# amp_diagram.net
KiCad netlist of a schematic drawn in EAGLE
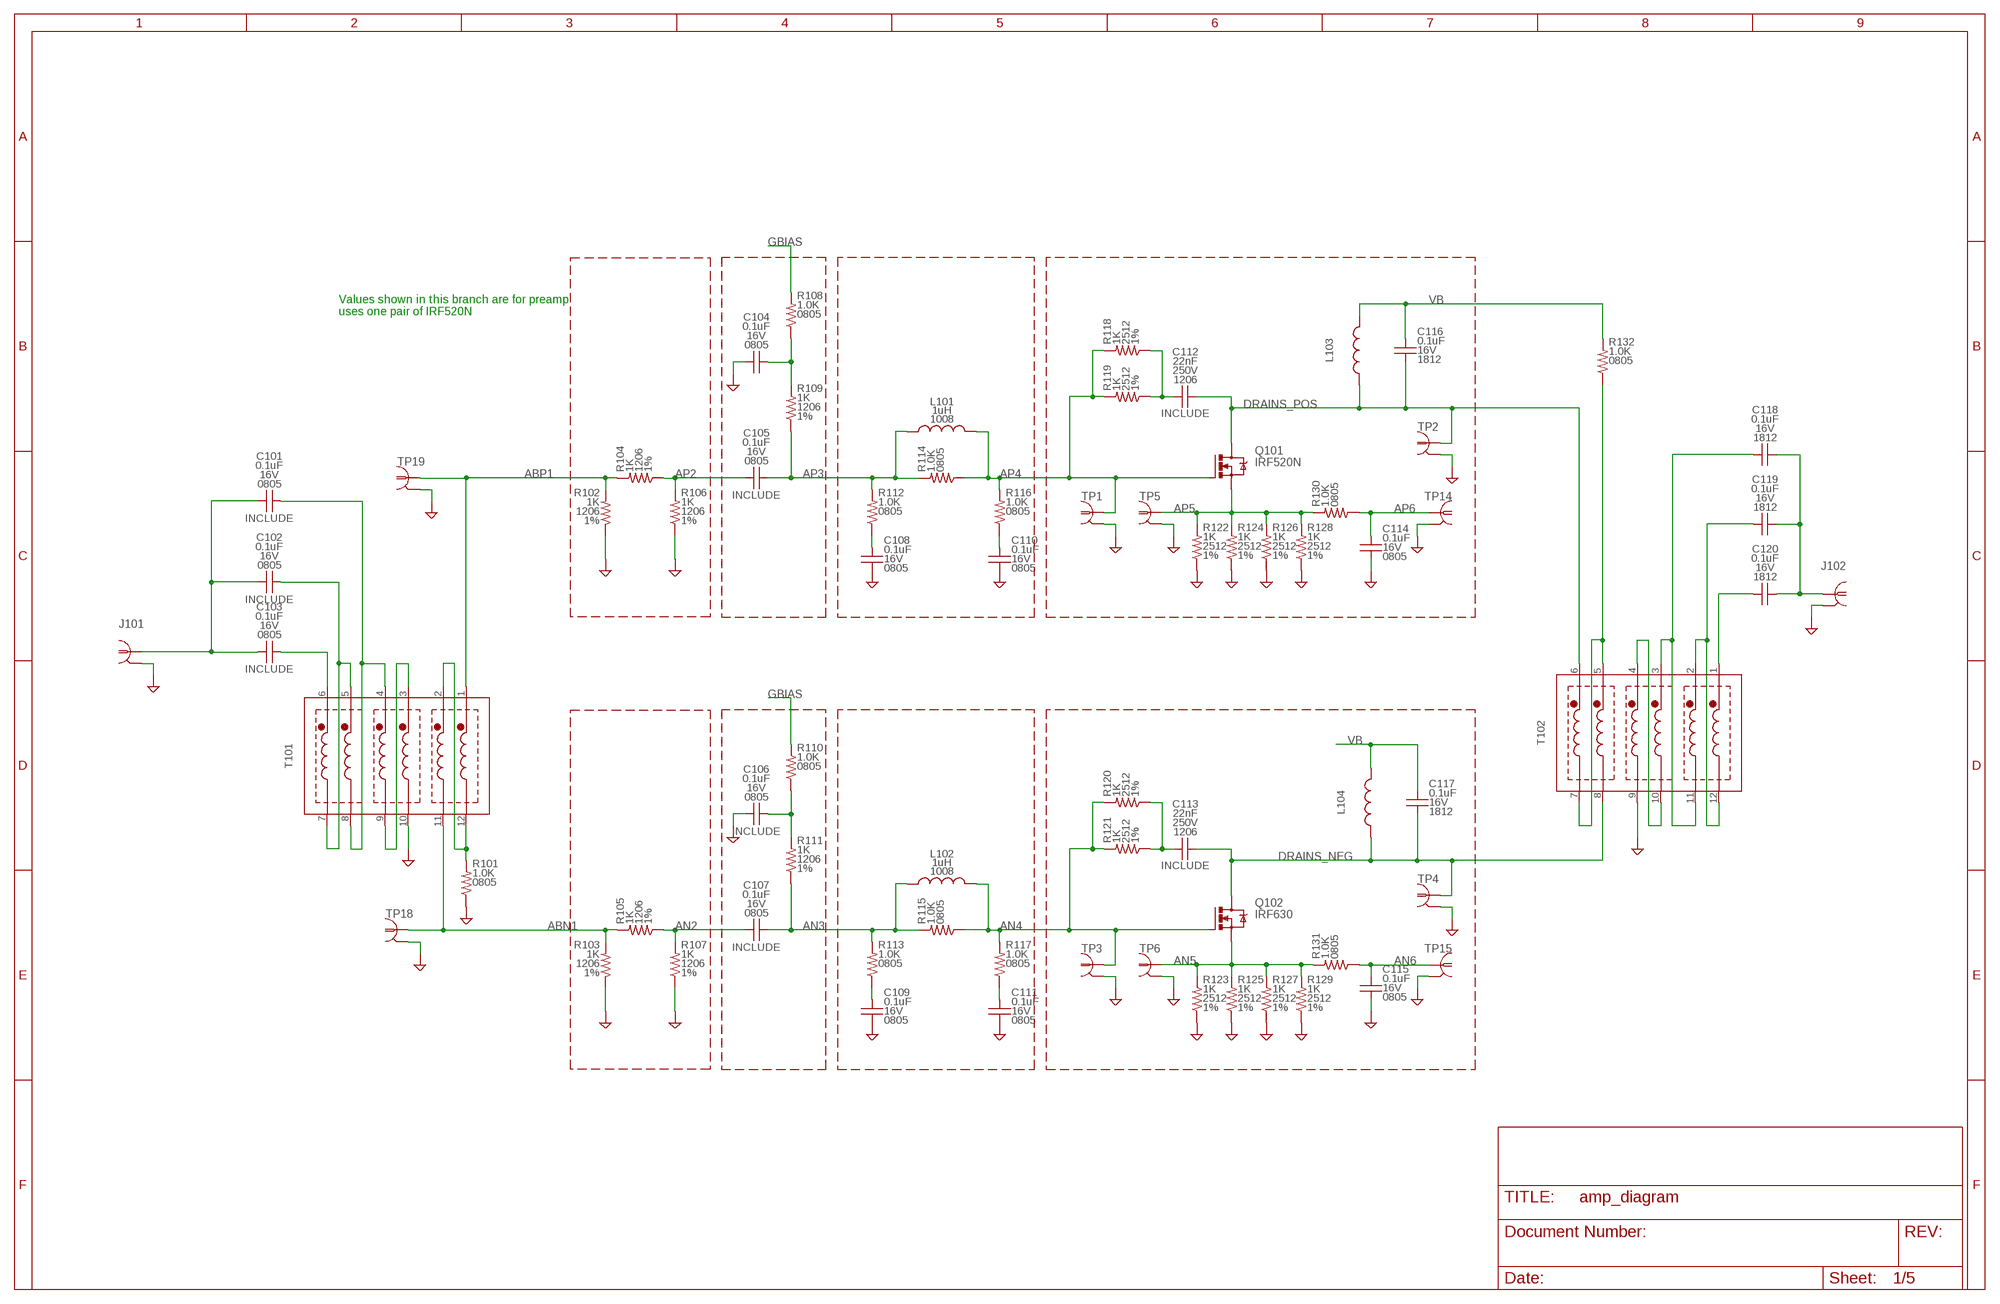
[diagram p0: schematic, sheet 1, part 1 of 2]
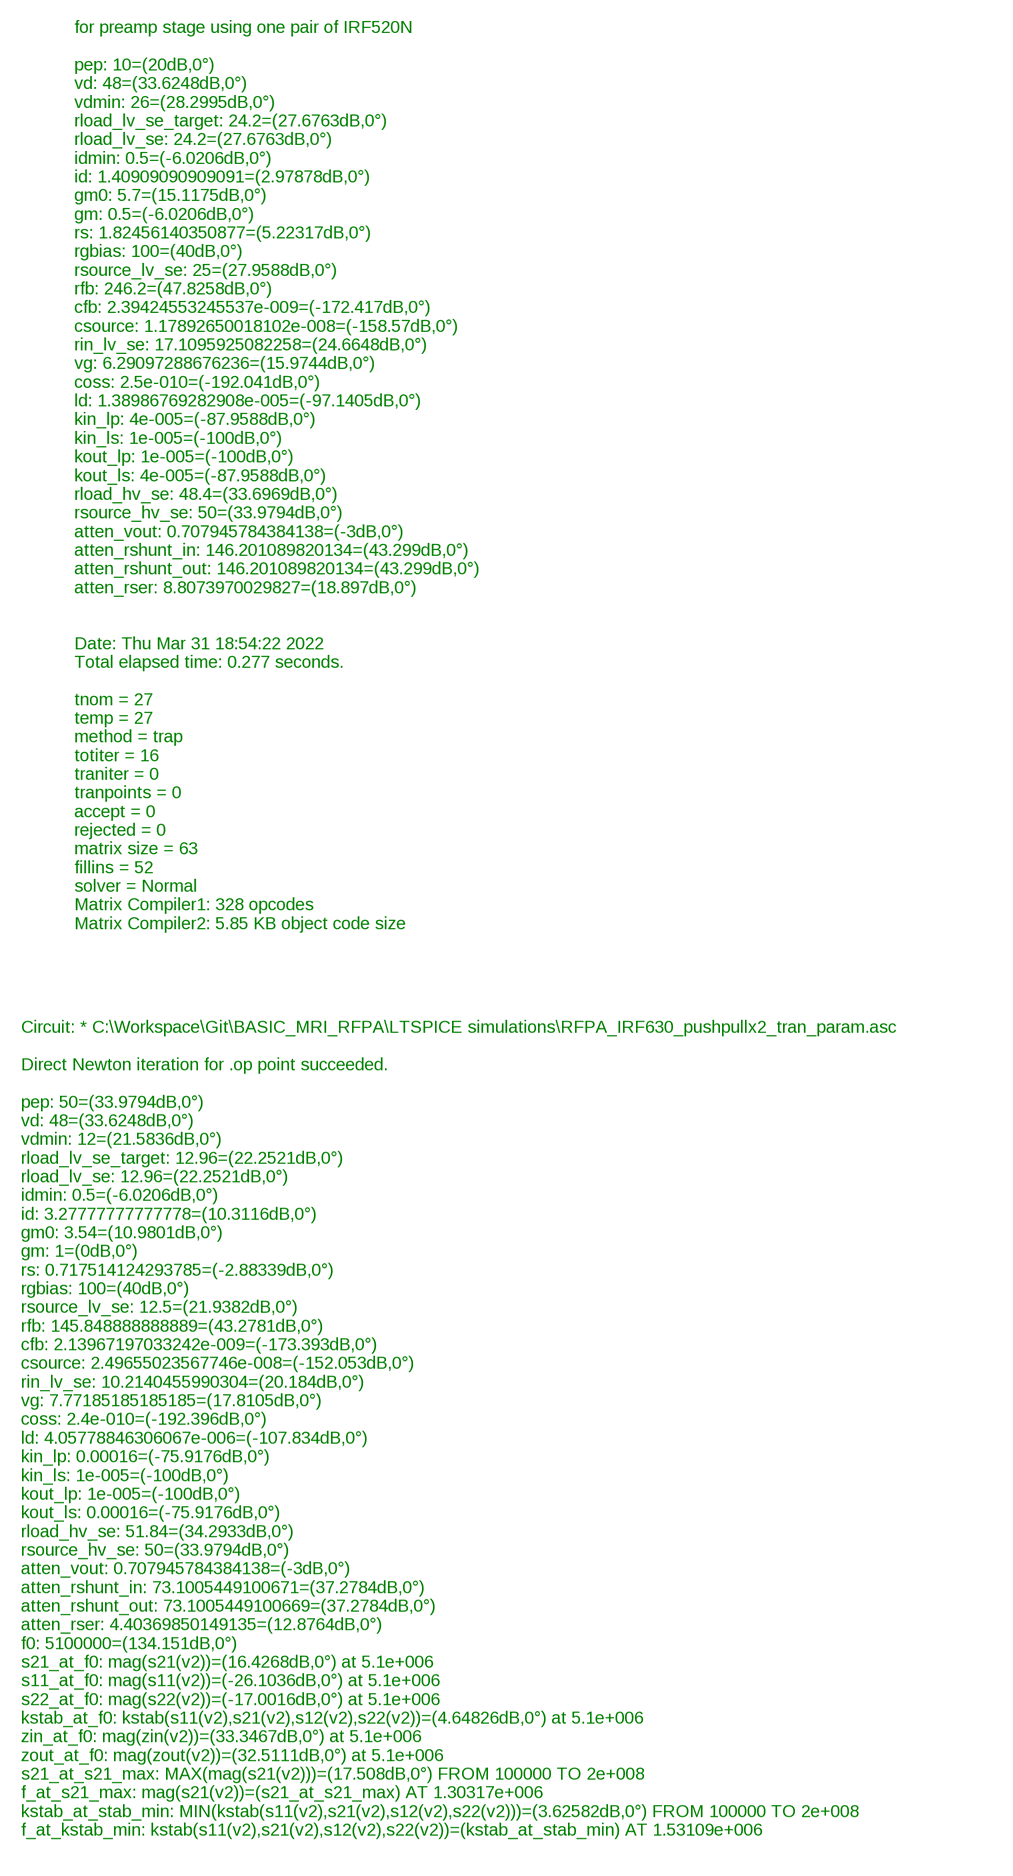
[diagram p1: schematic, sheet 1, part 2 of 2]
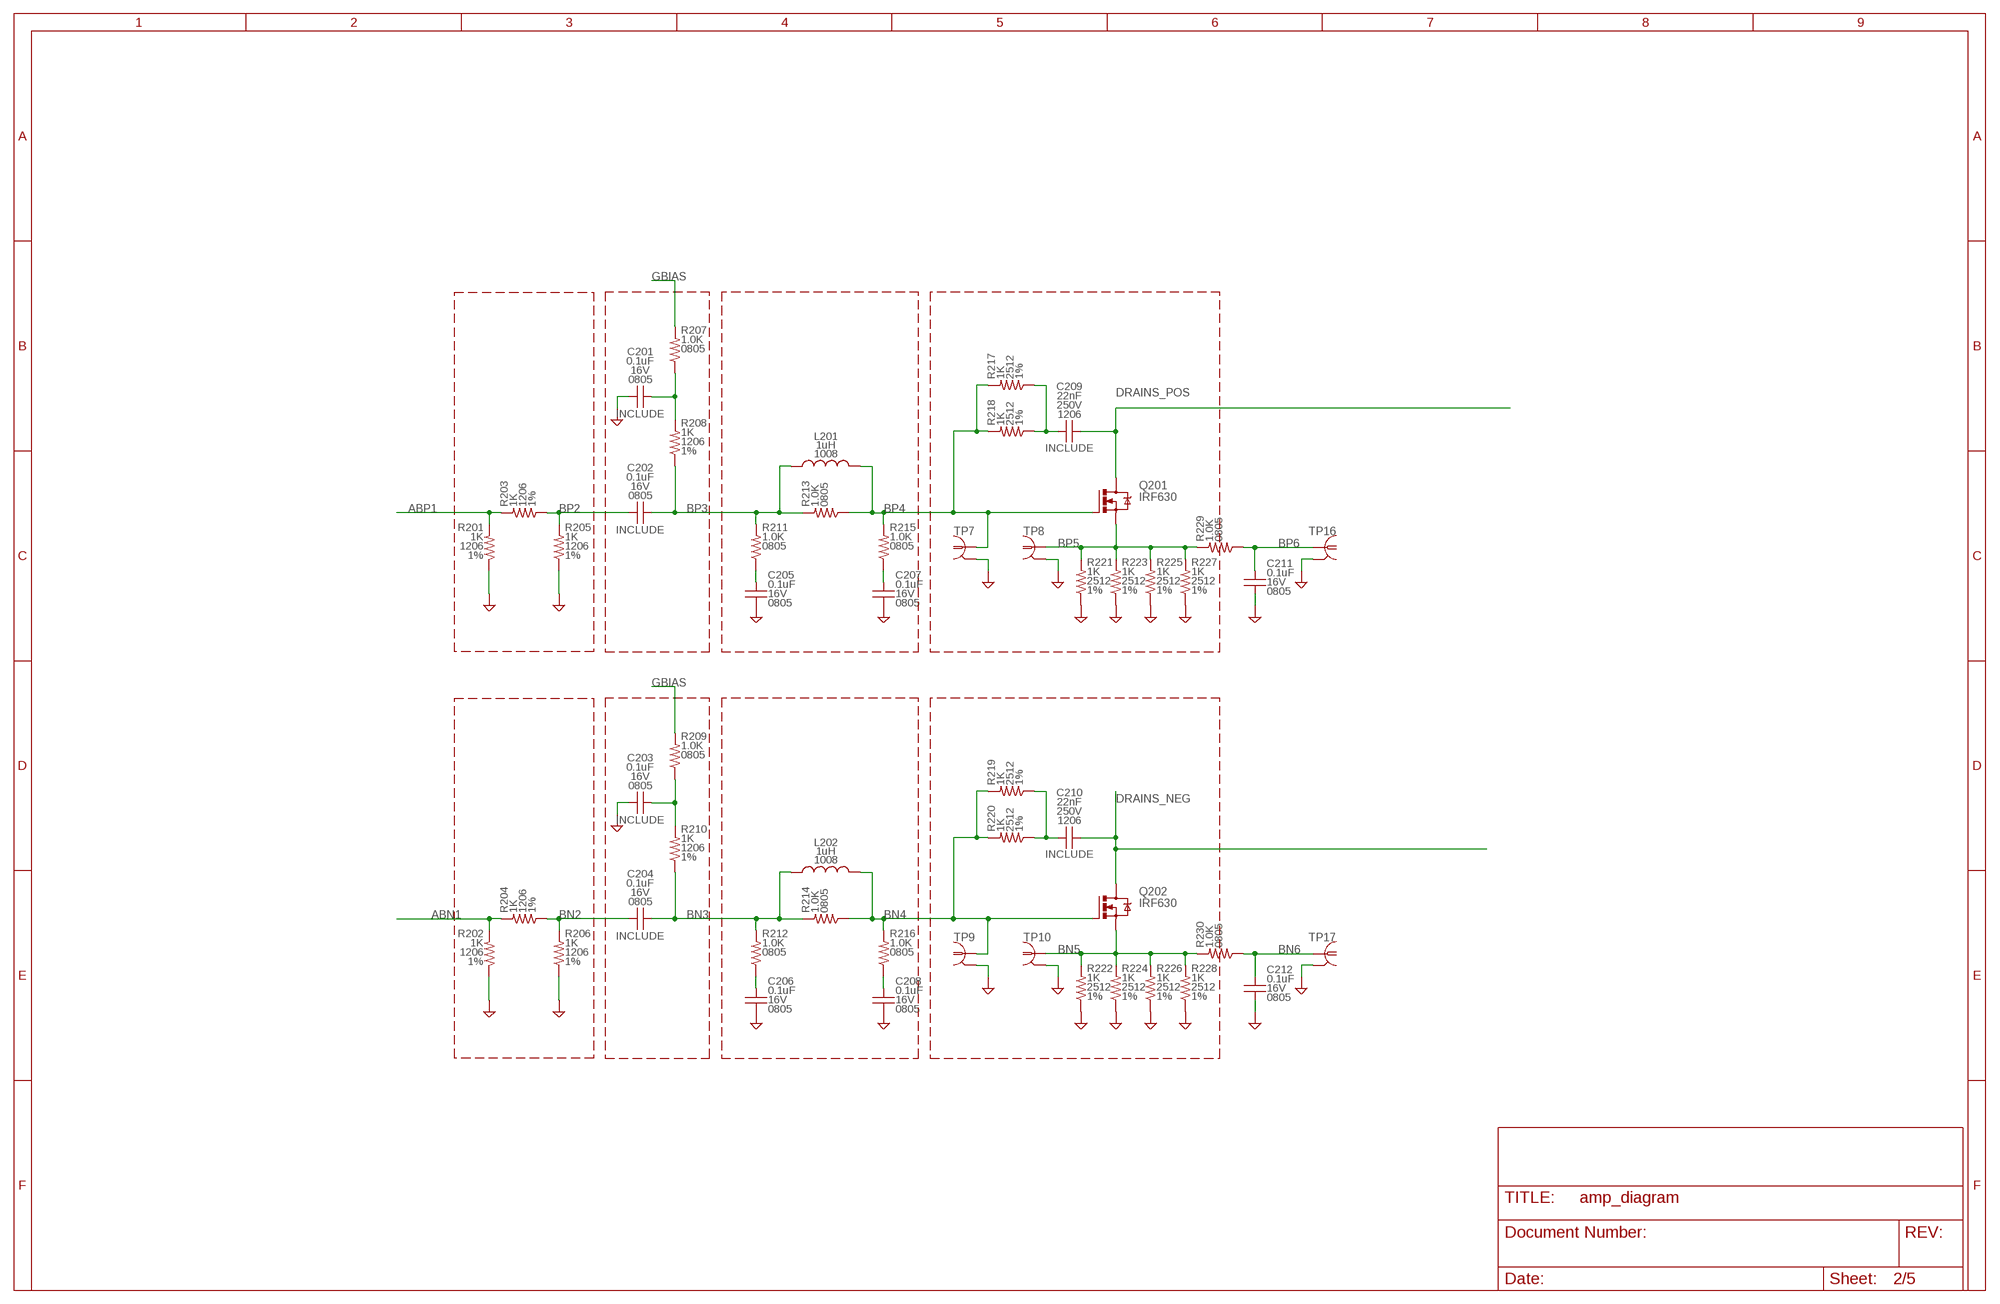
[diagram p2: schematic, sheet 2]
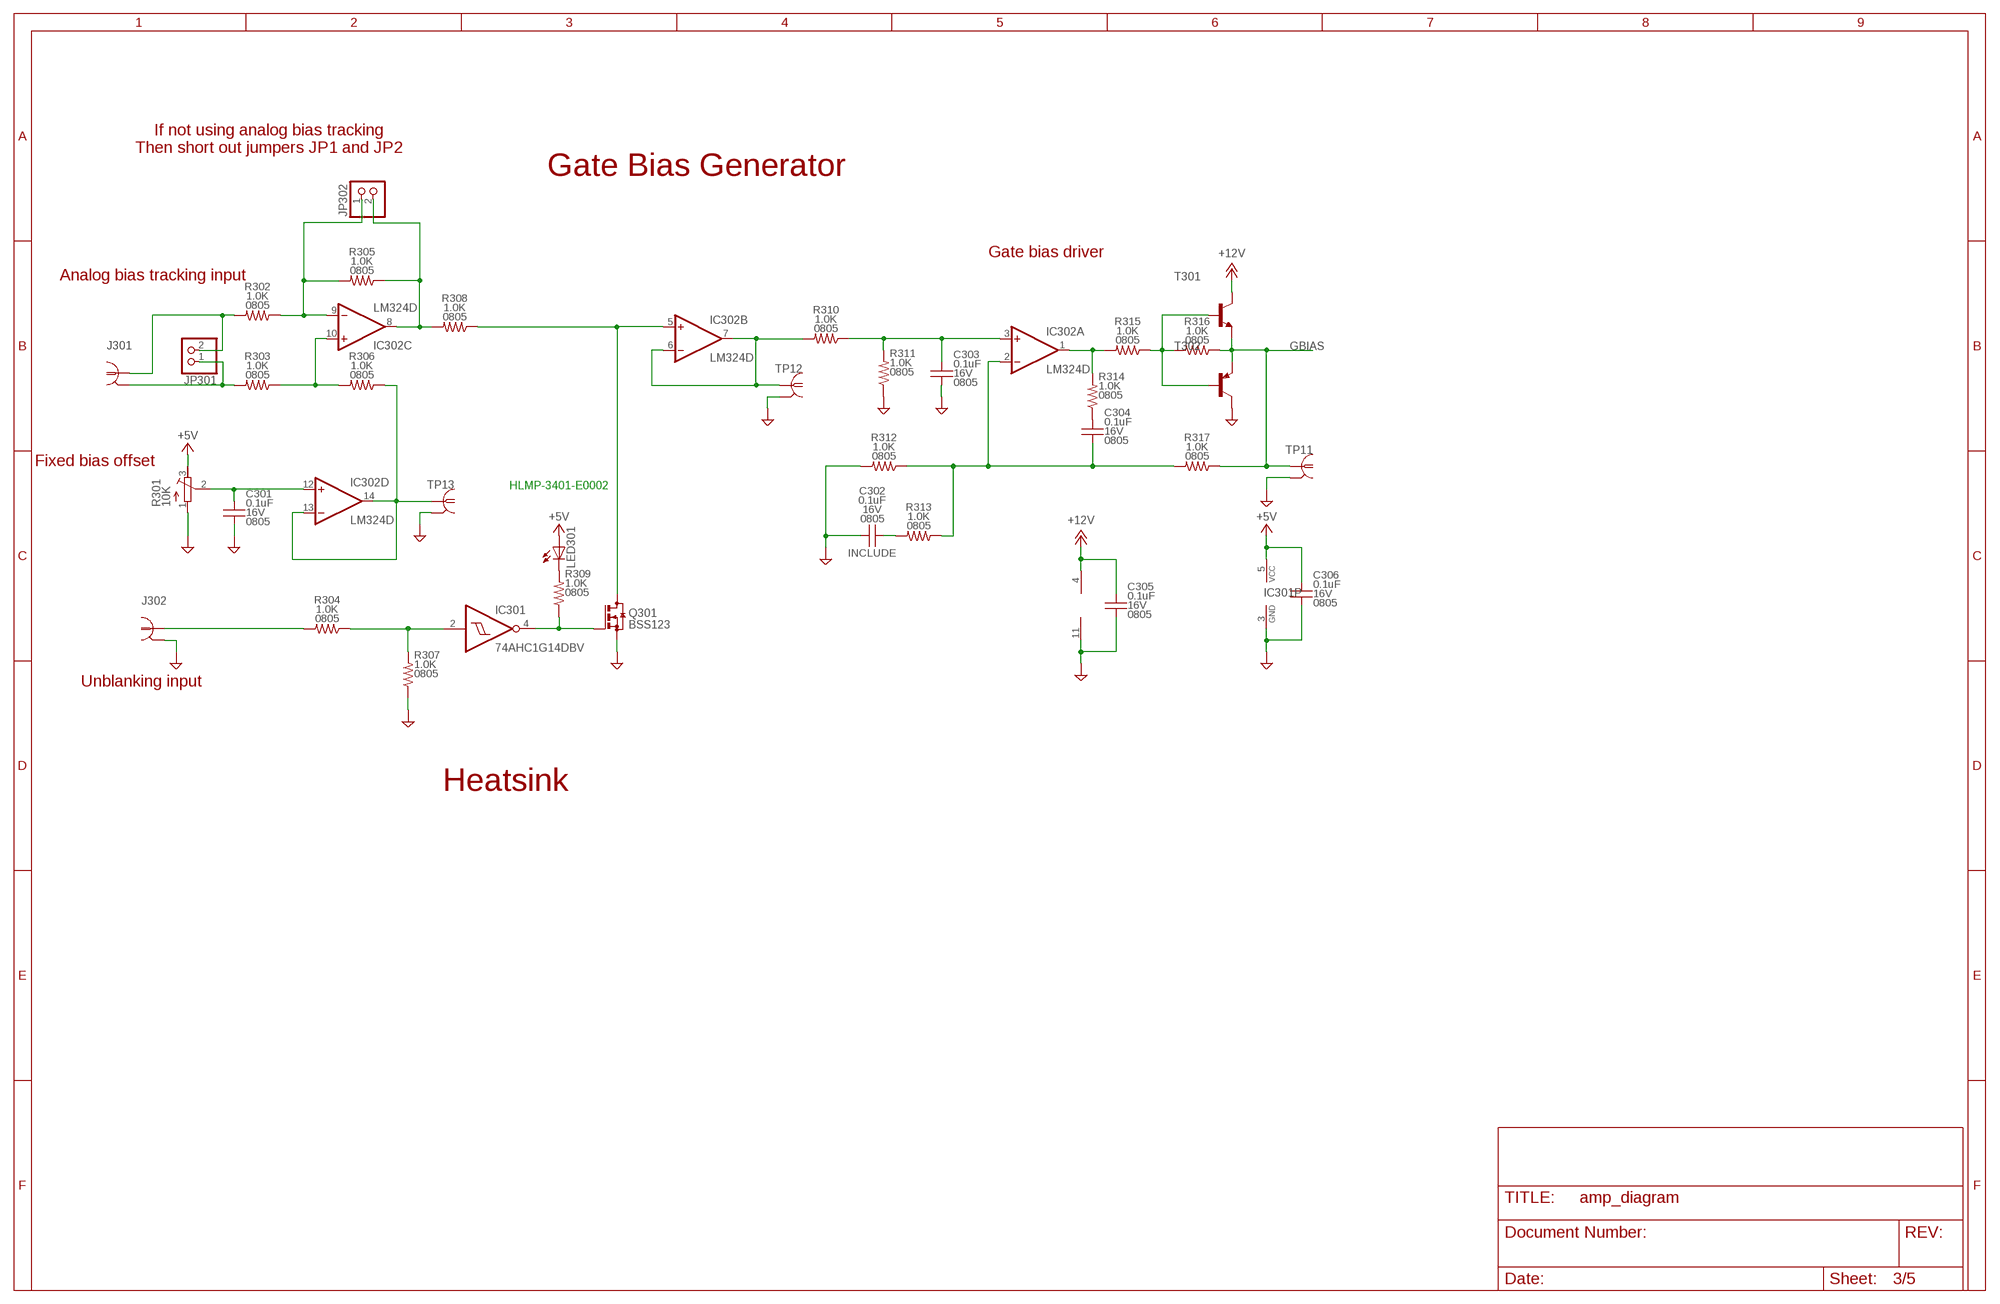
[diagram p3: schematic, sheet 3]
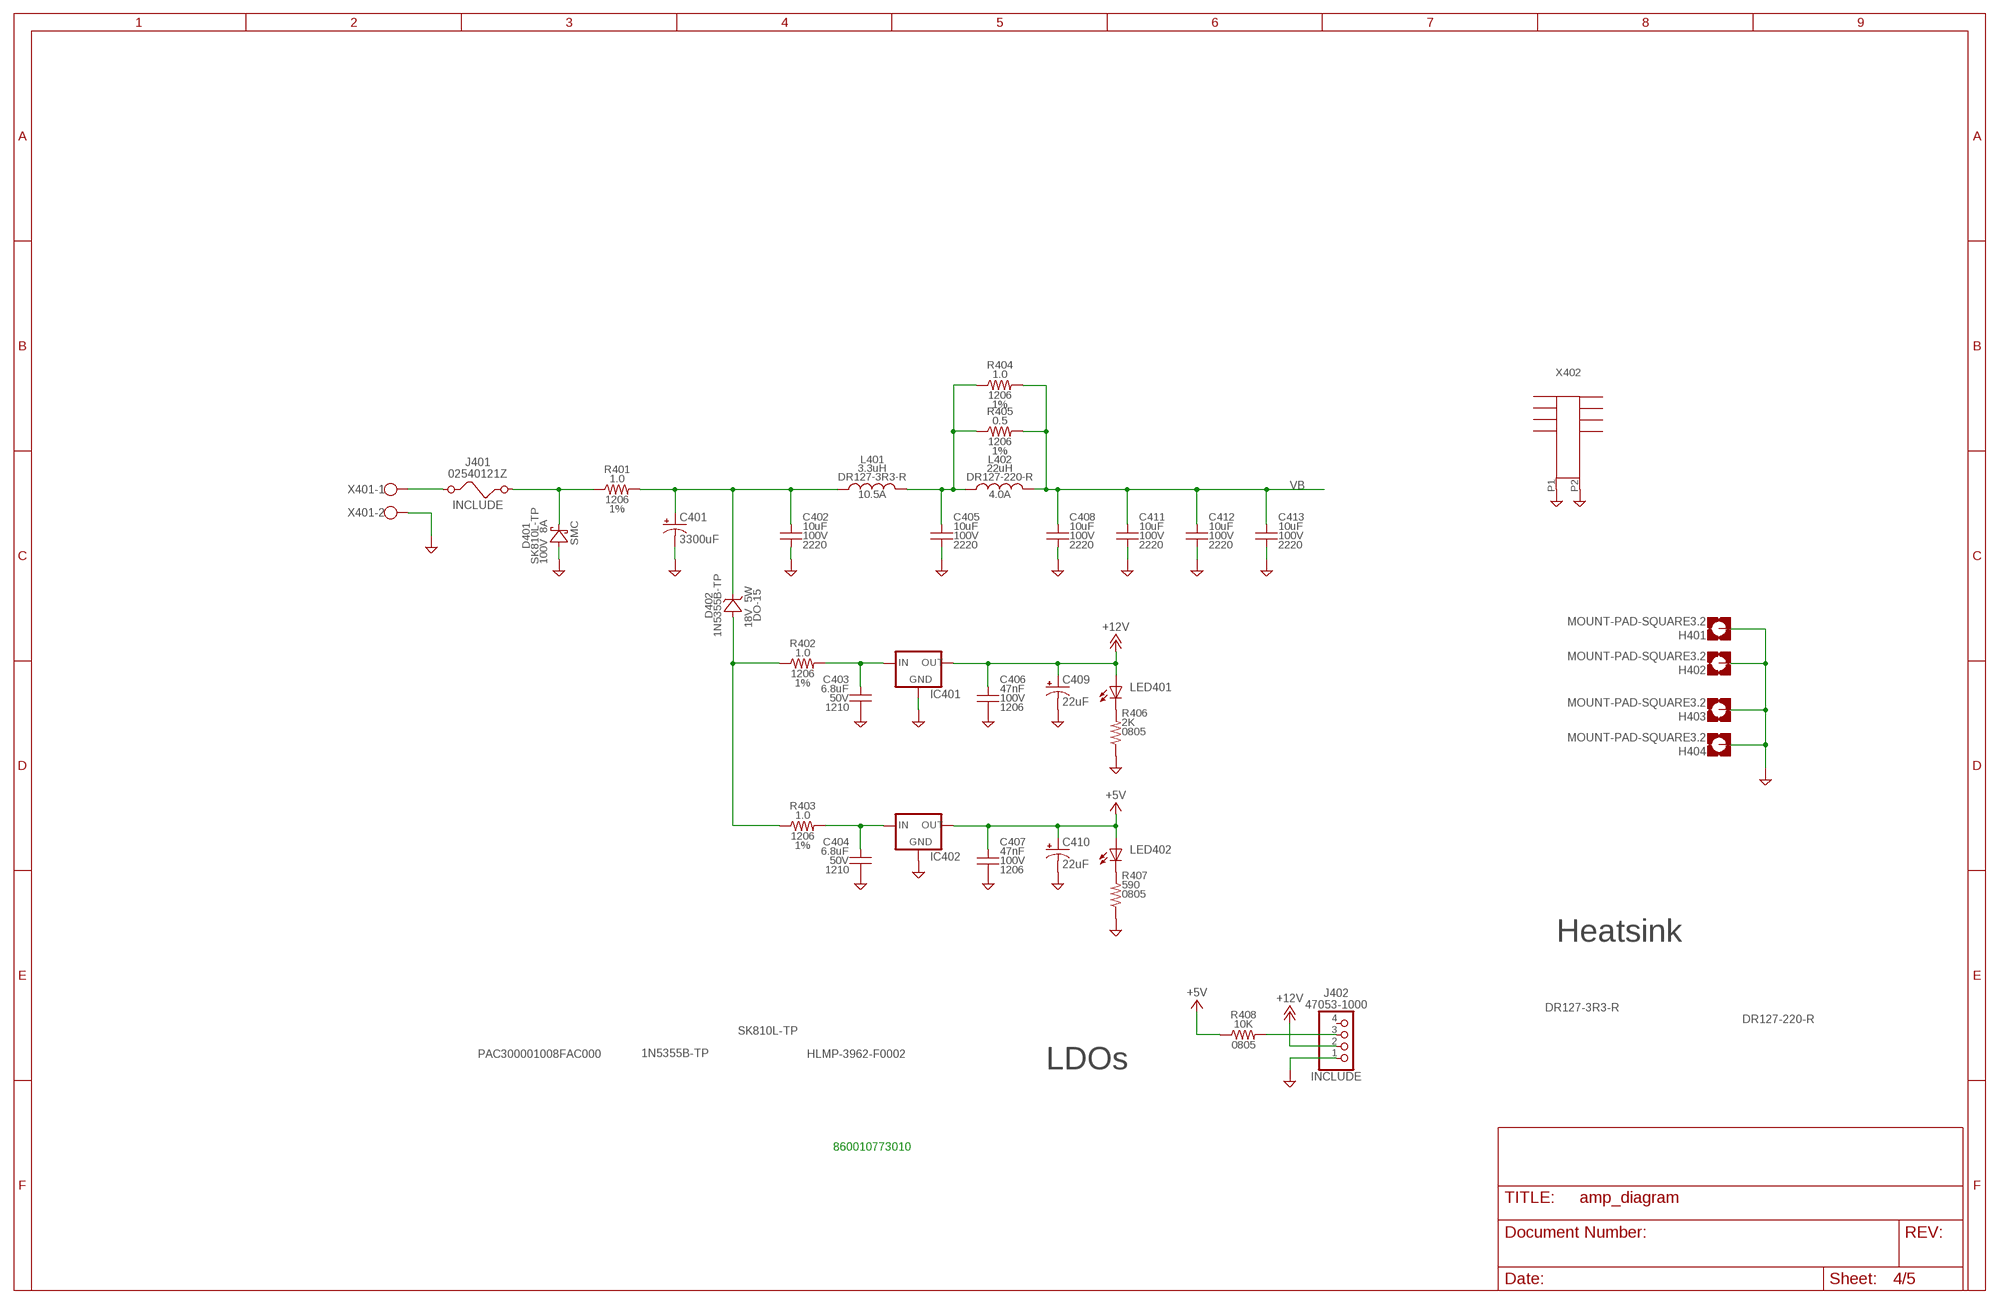
[diagram p4: schematic, sheet 4]
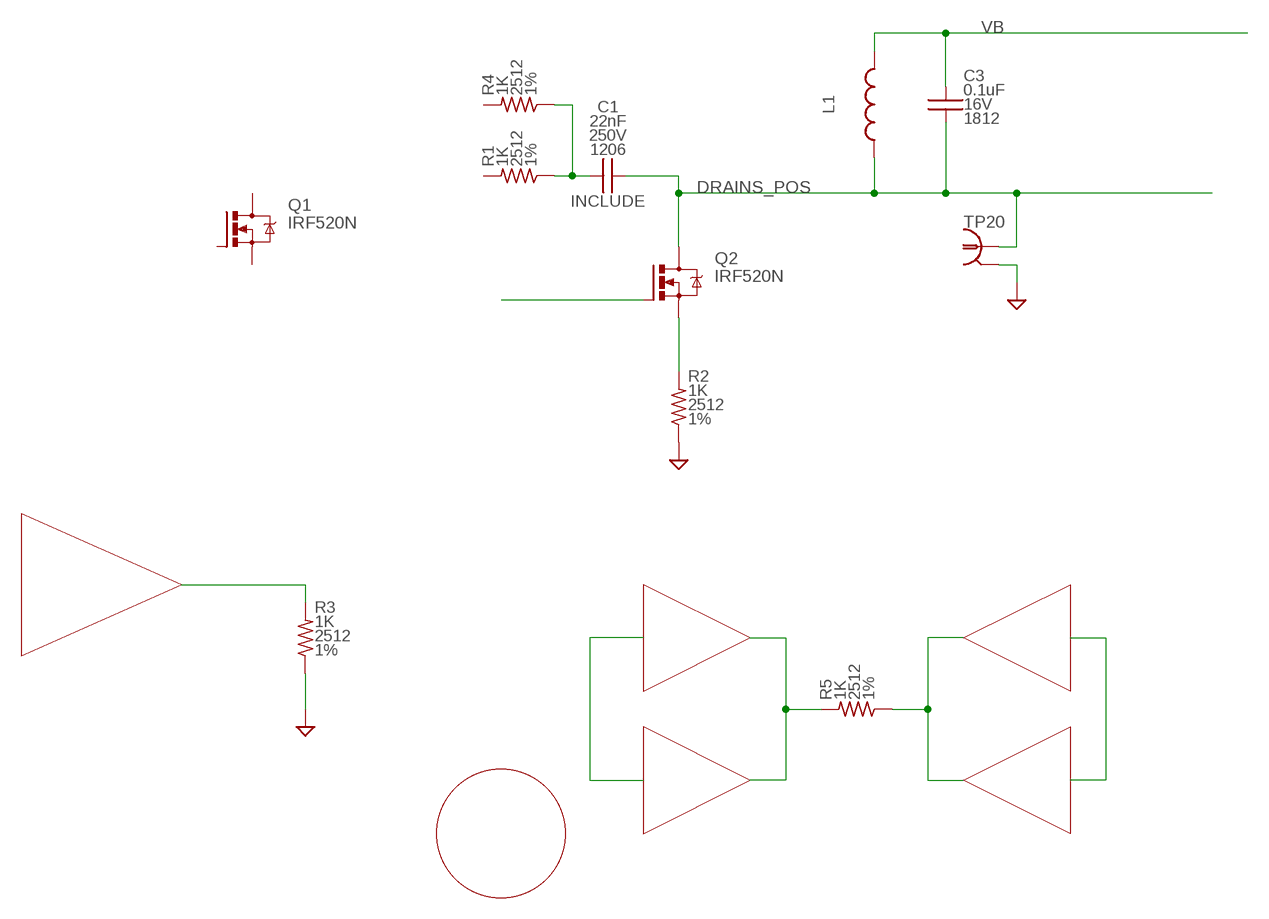
[diagram p5: schematic, sheet 5]

(export (version "E")
  (design (tool "Eeschema 10.0.6"))
  (components
    (comp (ref "C1")
      (value "22nF")
      (footprint "eagle-import:C1206")
      (fields
        (field (name "BOM") "INCLUDE")
        (field (name "PACKAGE") "1206")
        (field (name "PARTNO") "C3216NP02E223J160AA")
        (field (name "VOLTAGE") "250V")
      )
      (libsource (lib "eagle-import") (part "CC1206C-22N-250V-5%-1206-NP0"))
    )
    (comp (ref "C3")
      (value "0.1uF")
      (footprint "eagle-import:C1812")
      (fields (field (name "VOLTAGE") "16V"))
      (libsource (lib "eagle-import") (part "CC1812"))
    )
    (comp (ref "L1") (value "L") (footprint "eagle-import:DR127") (libsource (lib "eagle-import") (part "L")))
    (comp (ref "Q1")
      (value "IRF520N")
      (footprint "eagle-import:TO220BV")
      (libsource (lib "eagle-import") (part "IRF540"))
    )
    (comp (ref "Q2")
      (value "IRF520N")
      (footprint "eagle-import:TO220BV")
      (libsource (lib "eagle-import") (part "IRF540"))
    )
    (comp (ref "R1")
      (value "1K")
      (footprint "eagle-import:R2512")
      (fields (field (name "POWER") "1"))
      (libsource (lib "eagle-import") (part "RR2512R-1K-1%-2512-1W"))
    )
    (comp (ref "R2")
      (value "1K")
      (footprint "eagle-import:R2512")
      (fields (field (name "POWER") "1"))
      (libsource (lib "eagle-import") (part "RR2512R-1K-1%-2512-1W"))
    )
    (comp (ref "R3")
      (value "1K")
      (footprint "eagle-import:R2512")
      (fields (field (name "POWER") "1"))
      (libsource (lib "eagle-import") (part "RR2512R-1K-1%-2512-1W"))
    )
    (comp (ref "R4")
      (value "1K")
      (footprint "eagle-import:R2512")
      (fields (field (name "POWER") "1"))
      (libsource (lib "eagle-import") (part "RR2512R-1K-1%-2512-1W"))
    )
    (comp (ref "R5")
      (value "1K")
      (footprint "eagle-import:R2512")
      (fields (field (name "POWER") "1"))
      (libsource (lib "eagle-import") (part "RR2512R-1K-1%-2512-1W"))
    )
    (comp (ref "TP20")
      (value "PROBE_TPTP_7P5MM")
      (footprint "eagle-import:PROBE_TP_7P5MM")
      (libsource (lib "eagle-import") (part "PROBE_TPTP_7P5MM"))
    )
    (comp (ref "C301")
      (value "0.1uF")
      (footprint "eagle-import:0805_IPC-7351B")
      (fields (field (name "VOLTAGE") "16V"))
      (libsource (lib "eagle-import") (part "C0805_IPCC-0.1U-16V-0805-X7R"))
    )
    (comp (ref "C302")
      (value "0.1uF")
      (footprint "eagle-import:0805_IPC-7351B")
      (fields (field (name "PACKAGE") "0805") (field (name "VOLTAGE") "16V") (field (name "BOM") "INCLUDE"))
      (libsource (lib "eagle-import") (part "C0805_IPCC-0.1U-16V-0805-X7R"))
    )
    (comp (ref "C303")
      (value "0.1uF")
      (footprint "eagle-import:0805_IPC-7351B")
      (fields (field (name "VOLTAGE") "16V"))
      (libsource (lib "eagle-import") (part "C0805_IPCC-0.1U-16V-0805-X7R"))
    )
    (comp (ref "C304")
      (value "0.1uF")
      (footprint "eagle-import:0805_IPC-7351B")
      (fields (field (name "VOLTAGE") "16V"))
      (libsource (lib "eagle-import") (part "C0805_IPCC-0.1U-16V-0805-X7R"))
    )
    (comp (ref "C305")
      (value "0.1uF")
      (footprint "eagle-import:0805_IPC-7351B")
      (fields (field (name "VOLTAGE") "16V"))
      (libsource (lib "eagle-import") (part "C0805_IPCC-0.1U-16V-0805-X7R"))
    )
    (comp (ref "C306")
      (value "0.1uF")
      (footprint "eagle-import:0805_IPC-7351B")
      (fields (field (name "VOLTAGE") "16V"))
      (libsource (lib "eagle-import") (part "C0805_IPCC-0.1U-16V-0805-X7R"))
    )
    (comp (ref "IC301")
      (value "74AHC1G14DBV")
      (footprint "eagle-import:SOT23-5")
      (libsource (lib "eagle-import") (part "741G14DBVAHC"))
    )
    (comp (ref "IC302")
      (value "LM324D")
      (footprint "eagle-import:SO14")
      (libsource (lib "eagle-import") (part "LM324D"))
    )
    (comp (ref "J301")
      (value "COAXBNC_EDGE")
      (footprint "eagle-import:BNC_EDGE")
      (libsource (lib "eagle-import") (part "COAXBNC_EDGE"))
    )
    (comp (ref "J302")
      (value "COAXBNC_EDGE")
      (footprint "eagle-import:BNC_EDGE")
      (libsource (lib "eagle-import") (part "COAXBNC_EDGE"))
    )
    (comp (ref "JP301")
      (value "PINHD-1X2")
      (footprint "eagle-import:1X02")
      (libsource (lib "eagle-import") (part "PINHD-1X2"))
    )
    (comp (ref "JP302")
      (value "PINHD-1X2")
      (footprint "eagle-import:1X02")
      (libsource (lib "eagle-import") (part "PINHD-1X2"))
    )
    (comp (ref "LED301")
      (value "LED5MM")
      (footprint "eagle-import:LED5MM")
      (libsource (lib "eagle-import") (part "LED5MM"))
    )
    (comp (ref "Q301")
      (value "BSS123")
      (footprint "eagle-import:SOT23")
      (libsource (lib "eagle-import") (part "BSS123"))
    )
    (comp (ref "R301")
      (value "10K")
      (footprint "eagle-import:RTRIM3299W")
      (libsource (lib "eagle-import") (part "R-TRIMM3299W"))
    )
    (comp (ref "R302")
      (value "1.0K")
      (footprint "eagle-import:0805_IPC-7351B")
      (fields (field (name "PACKAGE") "0805"))
      (libsource (lib "eagle-import") (part "R0805_IPCR-1.0K-0.1%-0805-0.1W"))
    )
    (comp (ref "R303")
      (value "1.0K")
      (footprint "eagle-import:0805_IPC-7351B")
      (fields (field (name "PACKAGE") "0805"))
      (libsource (lib "eagle-import") (part "R0805_IPCR-1.0K-0.1%-0805-0.1W"))
    )
    (comp (ref "R304")
      (value "1.0K")
      (footprint "eagle-import:0805_IPC-7351B")
      (fields (field (name "PACKAGE") "0805"))
      (libsource (lib "eagle-import") (part "R0805_IPCR-1.0K-0.1%-0805-0.1W"))
    )
    (comp (ref "R305")
      (value "1.0K")
      (footprint "eagle-import:0805_IPC-7351B")
      (fields (field (name "PACKAGE") "0805"))
      (libsource (lib "eagle-import") (part "R0805_IPCR-1.0K-0.1%-0805-0.1W"))
    )
    (comp (ref "R306")
      (value "1.0K")
      (footprint "eagle-import:0805_IPC-7351B")
      (fields (field (name "PACKAGE") "0805"))
      (libsource (lib "eagle-import") (part "R0805_IPCR-1.0K-0.1%-0805-0.1W"))
    )
    (comp (ref "R307")
      (value "1.0K")
      (footprint "eagle-import:0805_IPC-7351B")
      (libsource (lib "eagle-import") (part "R0805_IPCR-1.0K-0.1%-0805-0.1W"))
    )
    (comp (ref "R308")
      (value "1.0K")
      (footprint "eagle-import:0805_IPC-7351B")
      (fields (field (name "PACKAGE") "0805"))
      (libsource (lib "eagle-import") (part "R0805_IPCR-1.0K-0.1%-0805-0.1W"))
    )
    (comp (ref "R309")
      (value "1.0K")
      (footprint "eagle-import:0805_IPC-7351B")
      (libsource (lib "eagle-import") (part "R0805_IPCR-1.0K-0.1%-0805-0.1W"))
    )
    (comp (ref "R310")
      (value "1.0K")
      (footprint "eagle-import:0805_IPC-7351B")
      (fields (field (name "PACKAGE") "0805"))
      (libsource (lib "eagle-import") (part "R0805_IPCR-1.0K-0.1%-0805-0.1W"))
    )
    (comp (ref "R311")
      (value "1.0K")
      (footprint "eagle-import:0805_IPC-7351B")
      (libsource (lib "eagle-import") (part "R0805_IPCR-1.0K-0.1%-0805-0.1W"))
    )
    (comp (ref "R312")
      (value "1.0K")
      (footprint "eagle-import:0805_IPC-7351B")
      (fields (field (name "PACKAGE") "0805"))
      (libsource (lib "eagle-import") (part "R0805_IPCR-1.0K-0.1%-0805-0.1W"))
    )
    (comp (ref "R313")
      (value "1.0K")
      (footprint "eagle-import:0805_IPC-7351B")
      (fields (field (name "PACKAGE") "0805"))
      (libsource (lib "eagle-import") (part "R0805_IPCR-1.0K-0.1%-0805-0.1W"))
    )
    (comp (ref "R314")
      (value "1.0K")
      (footprint "eagle-import:0805_IPC-7351B")
      (libsource (lib "eagle-import") (part "R0805_IPCR-1.0K-0.1%-0805-0.1W"))
    )
    (comp (ref "R315")
      (value "1.0K")
      (footprint "eagle-import:0805_IPC-7351B")
      (fields (field (name "PACKAGE") "0805"))
      (libsource (lib "eagle-import") (part "R0805_IPCR-1.0K-0.1%-0805-0.1W"))
    )
    (comp (ref "R316")
      (value "1.0K")
      (footprint "eagle-import:0805_IPC-7351B")
      (fields (field (name "PACKAGE") "0805"))
      (libsource (lib "eagle-import") (part "R0805_IPCR-1.0K-0.1%-0805-0.1W"))
    )
    (comp (ref "R317")
      (value "1.0K")
      (footprint "eagle-import:0805_IPC-7351B")
      (fields (field (name "PACKAGE") "0805"))
      (libsource (lib "eagle-import") (part "R0805_IPCR-1.0K-0.1%-0805-0.1W"))
    )
    (comp (ref "T301")
      (value "BC808-NPN-SOT23-BEC")
      (footprint "eagle-import:SOT23-BEC")
      (libsource (lib "eagle-import") (part "-NPN-SOT23-BECBC808"))
    )
    (comp (ref "T302")
      (value "BC807-16-PNP-SOT23-BEC")
      (footprint "eagle-import:SOT23-BEC")
      (libsource (lib "eagle-import") (part "-PNP-SOT23-BECBC807-16"))
    )
    (comp (ref "TP11")
      (value "PROBE_TPTP_5MM")
      (footprint "eagle-import:PROBE_TP_5MM")
      (libsource (lib "eagle-import") (part "PROBE_TPTP_5MM"))
    )
    (comp (ref "TP12")
      (value "PROBE_TPTP_5MM")
      (footprint "eagle-import:PROBE_TP_5MM")
      (libsource (lib "eagle-import") (part "PROBE_TPTP_5MM"))
    )
    (comp (ref "TP13")
      (value "PROBE_TPTP_5MM")
      (footprint "eagle-import:PROBE_TP_5MM")
      (libsource (lib "eagle-import") (part "PROBE_TPTP_5MM"))
    )
    (comp (ref "C101")
      (value "0.1uF")
      (footprint "eagle-import:0805_IPC-7351B")
      (fields (field (name "PACKAGE") "0805") (field (name "VOLTAGE") "16V") (field (name "BOM") "INCLUDE"))
      (libsource (lib "eagle-import") (part "C0805_IPCC-0.1U-16V-0805-X7R"))
    )
    (comp (ref "C102")
      (value "0.1uF")
      (footprint "eagle-import:0805_IPC-7351B")
      (fields (field (name "PACKAGE") "0805") (field (name "VOLTAGE") "16V") (field (name "BOM") "INCLUDE"))
      (libsource (lib "eagle-import") (part "C0805_IPCC-0.1U-16V-0805-X7R"))
    )
    (comp (ref "C103")
      (value "0.1uF")
      (footprint "eagle-import:0805_IPC-7351B")
      (fields (field (name "PACKAGE") "0805") (field (name "VOLTAGE") "16V") (field (name "BOM") "INCLUDE"))
      (libsource (lib "eagle-import") (part "C0805_IPCC-0.1U-16V-0805-X7R"))
    )
    (comp (ref "C104")
      (value "0.1uF")
      (footprint "eagle-import:0805_IPC-7351B")
      (fields (field (name "PACKAGE") "0805") (field (name "VOLTAGE") "16V") (field (name "BOM") "INCLUDE"))
      (libsource (lib "eagle-import") (part "C0805_IPCC-0.1U-16V-0805-X7R"))
    )
    (comp (ref "C105")
      (value "0.1uF")
      (footprint "eagle-import:0805_IPC-7351B")
      (fields (field (name "PACKAGE") "0805") (field (name "VOLTAGE") "16V") (field (name "BOM") "INCLUDE"))
      (libsource (lib "eagle-import") (part "C0805_IPCC-0.1U-16V-0805-X7R"))
    )
    (comp (ref "C106")
      (value "0.1uF")
      (footprint "eagle-import:0805_IPC-7351B")
      (fields (field (name "PACKAGE") "0805") (field (name "VOLTAGE") "16V") (field (name "BOM") "INCLUDE"))
      (libsource (lib "eagle-import") (part "C0805_IPCC-0.1U-16V-0805-X7R"))
    )
    (comp (ref "C107")
      (value "0.1uF")
      (footprint "eagle-import:0805_IPC-7351B")
      (fields (field (name "PACKAGE") "0805") (field (name "VOLTAGE") "16V") (field (name "BOM") "INCLUDE"))
      (libsource (lib "eagle-import") (part "C0805_IPCC-0.1U-16V-0805-X7R"))
    )
    (comp (ref "C108")
      (value "0.1uF")
      (footprint "eagle-import:0805_IPC-7351B")
      (fields (field (name "VOLTAGE") "16V"))
      (libsource (lib "eagle-import") (part "C0805_IPCC-0.1U-16V-0805-X7R"))
    )
    (comp (ref "C109")
      (value "0.1uF")
      (footprint "eagle-import:0805_IPC-7351B")
      (fields (field (name "VOLTAGE") "16V"))
      (libsource (lib "eagle-import") (part "C0805_IPCC-0.1U-16V-0805-X7R"))
    )
    (comp (ref "C110")
      (value "0.1uF")
      (footprint "eagle-import:0805_IPC-7351B")
      (fields (field (name "VOLTAGE") "16V"))
      (libsource (lib "eagle-import") (part "C0805_IPCC-0.1U-16V-0805-X7R"))
    )
    (comp (ref "C111")
      (value "0.1uF")
      (footprint "eagle-import:0805_IPC-7351B")
      (fields (field (name "VOLTAGE") "16V"))
      (libsource (lib "eagle-import") (part "C0805_IPCC-0.1U-16V-0805-X7R"))
    )
    (comp (ref "C112")
      (value "22nF")
      (footprint "eagle-import:C1206")
      (fields
        (field (name "BOM") "INCLUDE")
        (field (name "PACKAGE") "1206")
        (field (name "PARTNO") "C3216NP02E223J160AA")
        (field (name "VOLTAGE") "250V")
      )
      (libsource (lib "eagle-import") (part "CC1206C-22N-250V-5%-1206-NP0"))
    )
    (comp (ref "C113")
      (value "22nF")
      (footprint "eagle-import:C1206")
      (fields
        (field (name "BOM") "INCLUDE")
        (field (name "PACKAGE") "1206")
        (field (name "PARTNO") "C3216NP02E223J160AA")
        (field (name "VOLTAGE") "250V")
      )
      (libsource (lib "eagle-import") (part "CC1206C-22N-250V-5%-1206-NP0"))
    )
    (comp (ref "C114")
      (value "0.1uF")
      (footprint "eagle-import:0805_IPC-7351B")
      (fields (field (name "VOLTAGE") "16V"))
      (libsource (lib "eagle-import") (part "C0805_IPCC-0.1U-16V-0805-X7R"))
    )
    (comp (ref "C115")
      (value "0.1uF")
      (footprint "eagle-import:0805_IPC-7351B")
      (fields (field (name "VOLTAGE") "16V"))
      (libsource (lib "eagle-import") (part "C0805_IPCC-0.1U-16V-0805-X7R"))
    )
    (comp (ref "C116")
      (value "0.1uF")
      (footprint "eagle-import:C1812")
      (fields (field (name "VOLTAGE") "16V"))
      (libsource (lib "eagle-import") (part "CC1812"))
    )
    (comp (ref "C117")
      (value "0.1uF")
      (footprint "eagle-import:C1812")
      (fields (field (name "VOLTAGE") "16V"))
      (libsource (lib "eagle-import") (part "CC1812"))
    )
    (comp (ref "C118")
      (value "0.1uF")
      (footprint "eagle-import:C1812")
      (fields (field (name "VOLTAGE") "16V") (field (name "PACKAGE") "1812"))
      (libsource (lib "eagle-import") (part "CC1812"))
    )
    (comp (ref "C119")
      (value "0.1uF")
      (footprint "eagle-import:C1812")
      (fields (field (name "VOLTAGE") "16V") (field (name "PACKAGE") "1812"))
      (libsource (lib "eagle-import") (part "CC1812"))
    )
    (comp (ref "C120")
      (value "0.1uF")
      (footprint "eagle-import:C1812")
      (fields (field (name "VOLTAGE") "16V") (field (name "PACKAGE") "1812"))
      (libsource (lib "eagle-import") (part "CC1812"))
    )
    (comp (ref "J101")
      (value "COAXBNC_EDGE")
      (footprint "eagle-import:BNC_EDGE")
      (libsource (lib "eagle-import") (part "COAXBNC_EDGE"))
    )
    (comp (ref "J102")
      (value "COAXBNC_EDGE")
      (footprint "eagle-import:BNC_EDGE")
      (libsource (lib "eagle-import") (part "COAXBNC_EDGE"))
    )
    (comp (ref "L101")
      (value "1uH")
      (footprint "eagle-import:L1008")
      (fields (field (name "PARTNO") "1008CS-102XJEC"))
      (libsource (lib "eagle-import") (part "L_CHIP1008L-1.0U-AIR-5%-1008-0.37A"))
    )
    (comp (ref "L102")
      (value "1uH")
      (footprint "eagle-import:L1008")
      (fields (field (name "PARTNO") "1008CS-102XJEC"))
      (libsource (lib "eagle-import") (part "L_CHIP1008L-1.0U-AIR-5%-1008-0.37A"))
    )
    (comp (ref "L103")
      (value "L")
      (footprint "eagle-import:DR127")
      (libsource (lib "eagle-import") (part "L"))
    )
    (comp (ref "L104")
      (value "L")
      (footprint "eagle-import:DR127")
      (libsource (lib "eagle-import") (part "L"))
    )
    (comp (ref "Q101")
      (value "IRF520N")
      (footprint "eagle-import:TO220BV")
      (libsource (lib "eagle-import") (part "IRF540"))
    )
    (comp (ref "Q102")
      (value "IRF630")
      (footprint "eagle-import:TO220BV")
      (libsource (lib "eagle-import") (part "IRF540"))
    )
    (comp (ref "R101")
      (value "1.0K")
      (footprint "eagle-import:0805_IPC-7351B")
      (libsource (lib "eagle-import") (part "R0805_IPCR-1.0K-0.1%-0805-0.1W"))
    )
    (comp (ref "R102")
      (value "1K")
      (footprint "eagle-import:R1206")
      (fields (field (name "POWER") "0.25"))
      (libsource (lib "eagle-import") (part "RR1206R-1.0K-1%-1206-0.25W"))
    )
    (comp (ref "R103")
      (value "1K")
      (footprint "eagle-import:R1206")
      (fields (field (name "POWER") "0.25"))
      (libsource (lib "eagle-import") (part "RR1206R-1.0K-1%-1206-0.25W"))
    )
    (comp (ref "R104")
      (value "1K")
      (footprint "eagle-import:R1206")
      (fields (field (name "POWER") "0.25"))
      (libsource (lib "eagle-import") (part "RR1206R-1.0K-1%-1206-0.25W"))
    )
    (comp (ref "R105")
      (value "1K")
      (footprint "eagle-import:R1206")
      (fields (field (name "POWER") "0.25"))
      (libsource (lib "eagle-import") (part "RR1206R-1.0K-1%-1206-0.25W"))
    )
    (comp (ref "R106")
      (value "1K")
      (footprint "eagle-import:R1206")
      (fields (field (name "POWER") "0.25"))
      (libsource (lib "eagle-import") (part "RR1206R-1.0K-1%-1206-0.25W"))
    )
    (comp (ref "R107")
      (value "1K")
      (footprint "eagle-import:R1206")
      (fields (field (name "POWER") "0.25"))
      (libsource (lib "eagle-import") (part "RR1206R-1.0K-1%-1206-0.25W"))
    )
    (comp (ref "R108")
      (value "1.0K")
      (footprint "eagle-import:0805_IPC-7351B")
      (libsource (lib "eagle-import") (part "R0805_IPCR-1.0K-0.1%-0805-0.1W"))
    )
    (comp (ref "R109")
      (value "1K")
      (footprint "eagle-import:R1206")
      (fields (field (name "POWER") "0.25"))
      (libsource (lib "eagle-import") (part "RR1206R-1.0K-1%-1206-0.25W"))
    )
    (comp (ref "R110")
      (value "1.0K")
      (footprint "eagle-import:0805_IPC-7351B")
      (libsource (lib "eagle-import") (part "R0805_IPCR-1.0K-0.1%-0805-0.1W"))
    )
    (comp (ref "R111")
      (value "1K")
      (footprint "eagle-import:R1206")
      (fields (field (name "POWER") "0.25"))
      (libsource (lib "eagle-import") (part "RR1206R-1.0K-1%-1206-0.25W"))
    )
    (comp (ref "R112")
      (value "1.0K")
      (footprint "eagle-import:0805_IPC-7351B")
      (libsource (lib "eagle-import") (part "R0805_IPCR-1.0K-0.1%-0805-0.1W"))
    )
    (comp (ref "R113")
      (value "1.0K")
      (footprint "eagle-import:0805_IPC-7351B")
      (libsource (lib "eagle-import") (part "R0805_IPCR-1.0K-0.1%-0805-0.1W"))
    )
    (comp (ref "R114")
      (value "1.0K")
      (footprint "eagle-import:0805_IPC-7351B")
      (libsource (lib "eagle-import") (part "R0805_IPCR-1.0K-0.1%-0805-0.1W"))
    )
    (comp (ref "R115")
      (value "1.0K")
      (footprint "eagle-import:0805_IPC-7351B")
      (libsource (lib "eagle-import") (part "R0805_IPCR-1.0K-0.1%-0805-0.1W"))
    )
    (comp (ref "R116")
      (value "1.0K")
      (footprint "eagle-import:0805_IPC-7351B")
      (libsource (lib "eagle-import") (part "R0805_IPCR-1.0K-0.1%-0805-0.1W"))
    )
    (comp (ref "R117")
      (value "1.0K")
      (footprint "eagle-import:0805_IPC-7351B")
      (libsource (lib "eagle-import") (part "R0805_IPCR-1.0K-0.1%-0805-0.1W"))
    )
    (comp (ref "R118")
      (value "1K")
      (footprint "eagle-import:R2512")
      (fields (field (name "POWER") "1"))
      (libsource (lib "eagle-import") (part "RR2512R-1K-1%-2512-1W"))
    )
    (comp (ref "R119")
      (value "1K")
      (footprint "eagle-import:R2512")
      (fields (field (name "POWER") "1"))
      (libsource (lib "eagle-import") (part "RR2512R-1K-1%-2512-1W"))
    )
    (comp (ref "R120")
      (value "1K")
      (footprint "eagle-import:R2512")
      (fields (field (name "POWER") "1"))
      (libsource (lib "eagle-import") (part "RR2512R-1K-1%-2512-1W"))
    )
    (comp (ref "R121")
      (value "1K")
      (footprint "eagle-import:R2512")
      (fields (field (name "POWER") "1"))
      (libsource (lib "eagle-import") (part "RR2512R-1K-1%-2512-1W"))
    )
    (comp (ref "R122")
      (value "1K")
      (footprint "eagle-import:R2512")
      (fields (field (name "POWER") "1"))
      (libsource (lib "eagle-import") (part "RR2512R-1K-1%-2512-1W"))
    )
    (comp (ref "R123")
      (value "1K")
      (footprint "eagle-import:R2512")
      (fields (field (name "POWER") "1"))
      (libsource (lib "eagle-import") (part "RR2512R-1K-1%-2512-1W"))
    )
    (comp (ref "R124")
      (value "1K")
      (footprint "eagle-import:R2512")
      (fields (field (name "POWER") "1"))
      (libsource (lib "eagle-import") (part "RR2512R-1K-1%-2512-1W"))
    )
    (comp (ref "R125")
      (value "1K")
      (footprint "eagle-import:R2512")
      (fields (field (name "POWER") "1"))
      (libsource (lib "eagle-import") (part "RR2512R-1K-1%-2512-1W"))
    )
    (comp (ref "R126")
      (value "1K")
      (footprint "eagle-import:R2512")
      (fields (field (name "POWER") "1"))
      (libsource (lib "eagle-import") (part "RR2512R-1K-1%-2512-1W"))
    )
    (comp (ref "R127")
      (value "1K")
      (footprint "eagle-import:R2512")
      (fields (field (name "POWER") "1"))
      (libsource (lib "eagle-import") (part "RR2512R-1K-1%-2512-1W"))
    )
    (comp (ref "R128")
      (value "1K")
      (footprint "eagle-import:R2512")
      (fields (field (name "POWER") "1"))
      (libsource (lib "eagle-import") (part "RR2512R-1K-1%-2512-1W"))
    )
    (comp (ref "R129")
      (value "1K")
      (footprint "eagle-import:R2512")
      (fields (field (name "POWER") "1"))
      (libsource (lib "eagle-import") (part "RR2512R-1K-1%-2512-1W"))
    )
    (comp (ref "R130")
      (value "1.0K")
      (footprint "eagle-import:0805_IPC-7351B")
      (fields (field (name "PACKAGE") "0805"))
      (libsource (lib "eagle-import") (part "R0805_IPCR-1.0K-0.1%-0805-0.1W"))
    )
    (comp (ref "R131")
      (value "1.0K")
      (footprint "eagle-import:0805_IPC-7351B")
      (libsource (lib "eagle-import") (part "R0805_IPCR-1.0K-0.1%-0805-0.1W"))
    )
    (comp (ref "R132")
      (value "1.0K")
      (footprint "eagle-import:0805_IPC-7351B")
      (libsource (lib "eagle-import") (part "R0805_IPCR-1.0K-0.1%-0805-0.1W"))
    )
    (comp (ref "T101")
      (value "HP4_TRAFO")
      (footprint "eagle-import:HP4")
      (libsource (lib "eagle-import") (part "HP4_TRAFO"))
    )
    (comp (ref "T102")
      (value "HP4_TRAFO")
      (footprint "eagle-import:HP4")
      (libsource (lib "eagle-import") (part "HP4_TRAFO"))
    )
    (comp (ref "TP1")
      (value "PROBE_TPTP_5MM")
      (footprint "eagle-import:PROBE_TP_5MM")
      (libsource (lib "eagle-import") (part "PROBE_TPTP_5MM"))
    )
    (comp (ref "TP2")
      (value "PROBE_TPTP_7P5MM")
      (footprint "eagle-import:PROBE_TP_7P5MM")
      (libsource (lib "eagle-import") (part "PROBE_TPTP_7P5MM"))
    )
    (comp (ref "TP3")
      (value "PROBE_TPTP_5MM")
      (footprint "eagle-import:PROBE_TP_5MM")
      (libsource (lib "eagle-import") (part "PROBE_TPTP_5MM"))
    )
    (comp (ref "TP4")
      (value "PROBE_TPTP_7P5MM")
      (footprint "eagle-import:PROBE_TP_7P5MM")
      (libsource (lib "eagle-import") (part "PROBE_TPTP_7P5MM"))
    )
    (comp (ref "TP5")
      (value "PROBE_TPTP_7P5MM")
      (footprint "eagle-import:PROBE_TP_7P5MM")
      (libsource (lib "eagle-import") (part "PROBE_TPTP_7P5MM"))
    )
    (comp (ref "TP6")
      (value "PROBE_TPTP_7P5MM")
      (footprint "eagle-import:PROBE_TP_7P5MM")
      (libsource (lib "eagle-import") (part "PROBE_TPTP_7P5MM"))
    )
    (comp (ref "TP14")
      (value "PROBE_TPTP_5MM")
      (footprint "eagle-import:PROBE_TP_5MM")
      (libsource (lib "eagle-import") (part "PROBE_TPTP_5MM"))
    )
    (comp (ref "TP15")
      (value "PROBE_TPTP_5MM")
      (footprint "eagle-import:PROBE_TP_5MM")
      (libsource (lib "eagle-import") (part "PROBE_TPTP_5MM"))
    )
    (comp (ref "TP18")
      (value "PROBE_TPTP_5MM")
      (footprint "eagle-import:PROBE_TP_5MM")
      (libsource (lib "eagle-import") (part "PROBE_TPTP_5MM"))
    )
    (comp (ref "TP19")
      (value "PROBE_TPTP_5MM")
      (footprint "eagle-import:PROBE_TP_5MM")
      (libsource (lib "eagle-import") (part "PROBE_TPTP_5MM"))
    )
    (comp (ref "C401")
      (value "3300uF")
      (footprint "eagle-import:EB25D")
      (libsource (lib "eagle-import") (part "CPOL-USE10-25"))
    )
    (comp (ref "C402")
      (value "10uF")
      (footprint "eagle-import:C2220_CKG57N")
      (fields
        (field (name "BOM") "INCLUDE")
        (field (name "PACKAGE") "2220")
        (field (name "PARTNO") "CGA9N3X7S2A106M230KE")
        (field (name "VOLTAGE") "100V")
      )
      (libsource (lib "eagle-import") (part "CC2220_CKG57NCC-10U-100V-20%-2220-X7T"))
    )
    (comp (ref "C403")
      (value "6.8uF")
      (footprint "eagle-import:C1210")
      (fields (field (name "PARTNO") "CGA6P3X7S1H685K250AB") (field (name "VOLTAGE") "50V"))
      (libsource (lib "eagle-import") (part "CC1210CC-6.8U-50V-10%-1210-X7S"))
    )
    (comp (ref "C404")
      (value "6.8uF")
      (footprint "eagle-import:C1210")
      (fields (field (name "PARTNO") "CGA6P3X7S1H685K250AB") (field (name "VOLTAGE") "50V"))
      (libsource (lib "eagle-import") (part "CC1210CC-6.8U-50V-10%-1210-X7S"))
    )
    (comp (ref "C405")
      (value "10uF")
      (footprint "eagle-import:C2220_CKG57N")
      (fields
        (field (name "BOM") "INCLUDE")
        (field (name "PACKAGE") "2220")
        (field (name "PARTNO") "CGA9N3X7S2A106M230KE")
        (field (name "VOLTAGE") "100V")
      )
      (libsource (lib "eagle-import") (part "CC2220_CKG57NCC-10U-100V-20%-2220-X7T"))
    )
    (comp (ref "C406")
      (value "47nF")
      (footprint "eagle-import:C1206")
      (fields (field (name "PARTNO") "C3216C0G2A473J115AC") (field (name "VOLTAGE") "100V"))
      (libsource (lib "eagle-import") (part "CC1206C-47N-100V-5%-1206-NP0"))
    )
    (comp (ref "C407")
      (value "47nF")
      (footprint "eagle-import:C1206")
      (fields (field (name "PARTNO") "C3216C0G2A473J115AC") (field (name "VOLTAGE") "100V"))
      (libsource (lib "eagle-import") (part "CC1206C-47N-100V-5%-1206-NP0"))
    )
    (comp (ref "C408")
      (value "10uF")
      (footprint "eagle-import:C2220_CKG57N")
      (fields (field (name "PARTNO") "CGA9N3X7S2A106M230KE") (field (name "VOLTAGE") "100V"))
      (libsource (lib "eagle-import") (part "CC2220_CKG57NCC-10U-100V-20%-2220-X7T"))
    )
    (comp (ref "C409")
      (value "22uF")
      (footprint "eagle-import:E2,5-7")
      (libsource (lib "eagle-import") (part "CPOL-USE2.5-7"))
    )
    (comp (ref "C410")
      (value "22uF")
      (footprint "eagle-import:E2,5-7")
      (libsource (lib "eagle-import") (part "CPOL-USE2.5-7"))
    )
    (comp (ref "C411")
      (value "10uF")
      (footprint "eagle-import:C2220_CKG57N")
      (fields (field (name "PARTNO") "CGA9N3X7S2A106M230KE") (field (name "VOLTAGE") "100V"))
      (libsource (lib "eagle-import") (part "CC2220_CKG57NCC-10U-100V-20%-2220-X7T"))
    )
    (comp (ref "C412")
      (value "10uF")
      (footprint "eagle-import:C2220_CKG57N")
      (fields (field (name "PARTNO") "CGA9N3X7S2A106M230KE") (field (name "VOLTAGE") "100V"))
      (libsource (lib "eagle-import") (part "CC2220_CKG57NCC-10U-100V-20%-2220-X7T"))
    )
    (comp (ref "C413")
      (value "10uF")
      (footprint "eagle-import:C2220_CKG57N")
      (fields (field (name "PARTNO") "CGA9N3X7S2A106M230KE") (field (name "VOLTAGE") "100V"))
      (libsource (lib "eagle-import") (part "CC2220_CKG57NCC-10U-100V-20%-2220-X7T"))
    )
    (comp (ref "D401")
      (value "D-SCHOTTKYSK810L-TPSMC")
      (footprint "eagle-import:DO-214AB(SMC)")
      (fields (field (name "PARTNO") "SK810L-TP") (field (name "VOLTAGE") "100V"))
      (libsource (lib "eagle-import") (part "D-SCHOTTKYSMCSK810L-TP"))
    )
    (comp (ref "D402")
      (value "D-ZENER1N5355B-TPDO15-12")
      (footprint "eagle-import:DO15-12")
      (fields (field (name "PARTNO") "1N5355B-TP") (field (name "POWER") "5W") (field (name "VOLTAGE") "18V"))
      (libsource (lib "eagle-import") (part "D-ZENERDO15-121N5355B-TP"))
    )
    (comp (ref "H401")
      (value "MOUNT-PAD-SQUARE3.2")
      (footprint "eagle-import:3,2-PAD-SQUARE")
      (libsource (lib "eagle-import") (part "MOUNT-PAD-SQUARE3.2"))
    )
    (comp (ref "H402")
      (value "MOUNT-PAD-SQUARE3.2")
      (footprint "eagle-import:3,2-PAD-SQUARE")
      (libsource (lib "eagle-import") (part "MOUNT-PAD-SQUARE3.2"))
    )
    (comp (ref "H403")
      (value "MOUNT-PAD-SQUARE3.2")
      (footprint "eagle-import:3,2-PAD-SQUARE")
      (libsource (lib "eagle-import") (part "MOUNT-PAD-SQUARE3.2"))
    )
    (comp (ref "H404")
      (value "MOUNT-PAD-SQUARE3.2")
      (footprint "eagle-import:3,2-PAD-SQUARE")
      (libsource (lib "eagle-import") (part "MOUNT-PAD-SQUARE3.2"))
    )
    (comp (ref "IC401")
      (value "78XXS")
      (footprint "eagle-import:78XXS")
      (libsource (lib "eagle-import") (part "78XXS"))
    )
    (comp (ref "IC402")
      (value "78XXS")
      (footprint "eagle-import:78XXS")
      (libsource (lib "eagle-import") (part "78XXS"))
    )
    (comp (ref "J401")
      (value "FUSE_2P")
      (footprint "eagle-import:02540121Z")
      (fields (field (name "PARTNO") "02540121Z"))
      (libsource (lib "eagle-import") (part "FUSE_2P"))
    )
    (comp (ref "J402")
      (value "KK_PCFAN")
      (footprint "eagle-import:47053-1000")
      (fields (field (name "PARTNO") "47053-1000"))
      (libsource (lib "eagle-import") (part "KK_PCFAN"))
    )
    (comp (ref "L401")
      (value "3.3uH")
      (footprint "eagle-import:DR127")
      (fields (field (name "PARTNO") "DR127-3R3-R"))
      (libsource (lib "eagle-import") (part "LL-3.3U-FERRITE-20%-12.5X12.5MM-10.5A"))
    )
    (comp (ref "L402")
      (value "22uH")
      (footprint "eagle-import:DR127")
      (fields (field (name "PARTNO") "DR127-220-R"))
      (libsource (lib "eagle-import") (part "LL-22U-FERRITE-20%-12.5X12.5MM-4A"))
    )
    (comp (ref "LED401")
      (value "LED5MM")
      (footprint "eagle-import:LED5MM")
      (libsource (lib "eagle-import") (part "LED5MM"))
    )
    (comp (ref "LED402")
      (value "LED5MM")
      (footprint "eagle-import:LED5MM")
      (libsource (lib "eagle-import") (part "LED5MM"))
    )
    (comp (ref "R401")
      (value "1.0")
      (footprint "eagle-import:R1206")
      (fields (field (name "POWER") "0.25"))
      (libsource (lib "eagle-import") (part "R90R1206R-1.0K-1%-1206-0.25W"))
    )
    (comp (ref "R402")
      (value "1.0")
      (footprint "eagle-import:R1206")
      (fields (field (name "POWER") "0.25"))
      (libsource (lib "eagle-import") (part "R90R1206R-1.0K-1%-1206-0.25W"))
    )
    (comp (ref "R403")
      (value "1.0")
      (footprint "eagle-import:R1206")
      (fields (field (name "POWER") "0.25"))
      (libsource (lib "eagle-import") (part "R90R1206R-1.0K-1%-1206-0.25W"))
    )
    (comp (ref "R404")
      (value "1.0")
      (footprint "eagle-import:R1206")
      (fields (field (name "POWER") "0.25"))
      (libsource (lib "eagle-import") (part "R90R1206R-1.0K-1%-1206-0.25W"))
    )
    (comp (ref "R405")
      (value "0.5")
      (footprint "eagle-import:R1206")
      (fields (field (name "POWER") "0.25"))
      (libsource (lib "eagle-import") (part "R90R1206R-1.0K-1%-1206-0.25W"))
    )
    (comp (ref "R406")
      (value "2K")
      (footprint "eagle-import:0805_IPC-7351B")
      (libsource (lib "eagle-import") (part "R0805_IPCR-1.0K-0.1%-0805-0.1W"))
    )
    (comp (ref "R407")
      (value "590")
      (footprint "eagle-import:0805_IPC-7351B")
      (libsource (lib "eagle-import") (part "R0805_IPCR-1.0K-0.1%-0805-0.1W"))
    )
    (comp (ref "R408")
      (value "10K")
      (footprint "eagle-import:0805_IPC-7351B")
      (libsource (lib "eagle-import") (part "R900805_IPCR-1.0K-0.1%-0805-0.1W"))
    )
    (comp (ref "X401")
      (value "W237-102")
      (footprint "eagle-import:W237-102")
      (fields (field (name "MPN") "237-102"))
      (libsource (lib "eagle-import") (part "W237-102"))
    )
    (comp (ref "X402")
      (value "HEATSINK_OMNI_DUAL30-75-D")
      (footprint "eagle-import:OMNI-UNI-30-75-D")
      (libsource (lib "eagle-import") (part "HEATSINK_OMNI_DUAL30-75-D"))
    )
    (comp (ref "C201")
      (value "0.1uF")
      (footprint "eagle-import:0805_IPC-7351B")
      (fields (field (name "PACKAGE") "0805") (field (name "VOLTAGE") "16V") (field (name "BOM") "INCLUDE"))
      (libsource (lib "eagle-import") (part "C0805_IPCC-0.1U-16V-0805-X7R"))
    )
    (comp (ref "C202")
      (value "0.1uF")
      (footprint "eagle-import:0805_IPC-7351B")
      (fields (field (name "PACKAGE") "0805") (field (name "VOLTAGE") "16V") (field (name "BOM") "INCLUDE"))
      (libsource (lib "eagle-import") (part "C0805_IPCC-0.1U-16V-0805-X7R"))
    )
    (comp (ref "C203")
      (value "0.1uF")
      (footprint "eagle-import:0805_IPC-7351B")
      (fields (field (name "PACKAGE") "0805") (field (name "VOLTAGE") "16V") (field (name "BOM") "INCLUDE"))
      (libsource (lib "eagle-import") (part "C0805_IPCC-0.1U-16V-0805-X7R"))
    )
    (comp (ref "C204")
      (value "0.1uF")
      (footprint "eagle-import:0805_IPC-7351B")
      (fields (field (name "PACKAGE") "0805") (field (name "VOLTAGE") "16V") (field (name "BOM") "INCLUDE"))
      (libsource (lib "eagle-import") (part "C0805_IPCC-0.1U-16V-0805-X7R"))
    )
    (comp (ref "C205")
      (value "0.1uF")
      (footprint "eagle-import:0805_IPC-7351B")
      (fields (field (name "VOLTAGE") "16V"))
      (libsource (lib "eagle-import") (part "C0805_IPCC-0.1U-16V-0805-X7R"))
    )
    (comp (ref "C206")
      (value "0.1uF")
      (footprint "eagle-import:0805_IPC-7351B")
      (fields (field (name "VOLTAGE") "16V"))
      (libsource (lib "eagle-import") (part "C0805_IPCC-0.1U-16V-0805-X7R"))
    )
    (comp (ref "C207")
      (value "0.1uF")
      (footprint "eagle-import:0805_IPC-7351B")
      (fields (field (name "VOLTAGE") "16V"))
      (libsource (lib "eagle-import") (part "C0805_IPCC-0.1U-16V-0805-X7R"))
    )
    (comp (ref "C208")
      (value "0.1uF")
      (footprint "eagle-import:0805_IPC-7351B")
      (fields (field (name "VOLTAGE") "16V"))
      (libsource (lib "eagle-import") (part "C0805_IPCC-0.1U-16V-0805-X7R"))
    )
    (comp (ref "C209")
      (value "22nF")
      (footprint "eagle-import:C1206")
      (fields
        (field (name "BOM") "INCLUDE")
        (field (name "PACKAGE") "1206")
        (field (name "PARTNO") "C3216NP02E223J160AA")
        (field (name "VOLTAGE") "250V")
      )
      (libsource (lib "eagle-import") (part "CC1206C-22N-250V-5%-1206-NP0"))
    )
    (comp (ref "C210")
      (value "22nF")
      (footprint "eagle-import:C1206")
      (fields
        (field (name "BOM") "INCLUDE")
        (field (name "PACKAGE") "1206")
        (field (name "PARTNO") "C3216NP02E223J160AA")
        (field (name "VOLTAGE") "250V")
      )
      (libsource (lib "eagle-import") (part "CC1206C-22N-250V-5%-1206-NP0"))
    )
    (comp (ref "C211")
      (value "0.1uF")
      (footprint "eagle-import:0805_IPC-7351B")
      (fields (field (name "VOLTAGE") "16V"))
      (libsource (lib "eagle-import") (part "C0805_IPCC-0.1U-16V-0805-X7R"))
    )
    (comp (ref "C212")
      (value "0.1uF")
      (footprint "eagle-import:0805_IPC-7351B")
      (fields (field (name "VOLTAGE") "16V"))
      (libsource (lib "eagle-import") (part "C0805_IPCC-0.1U-16V-0805-X7R"))
    )
    (comp (ref "L201")
      (value "1uH")
      (footprint "eagle-import:L1008")
      (fields (field (name "PARTNO") "1008CS-102XJEC"))
      (libsource (lib "eagle-import") (part "L_CHIP1008L-1.0U-AIR-5%-1008-0.37A"))
    )
    (comp (ref "L202")
      (value "1uH")
      (footprint "eagle-import:L1008")
      (fields (field (name "PARTNO") "1008CS-102XJEC"))
      (libsource (lib "eagle-import") (part "L_CHIP1008L-1.0U-AIR-5%-1008-0.37A"))
    )
    (comp (ref "Q201")
      (value "IRF630")
      (footprint "eagle-import:TO220BV")
      (libsource (lib "eagle-import") (part "IRF540"))
    )
    (comp (ref "Q202")
      (value "IRF630")
      (footprint "eagle-import:TO220BV")
      (libsource (lib "eagle-import") (part "IRF540"))
    )
    (comp (ref "R201")
      (value "1K")
      (footprint "eagle-import:R1206")
      (fields (field (name "POWER") "0.25"))
      (libsource (lib "eagle-import") (part "RR1206R-1.0K-1%-1206-0.25W"))
    )
    (comp (ref "R202")
      (value "1K")
      (footprint "eagle-import:R1206")
      (fields (field (name "POWER") "0.25"))
      (libsource (lib "eagle-import") (part "RR1206R-1.0K-1%-1206-0.25W"))
    )
    (comp (ref "R203")
      (value "1K")
      (footprint "eagle-import:R1206")
      (fields (field (name "POWER") "0.25"))
      (libsource (lib "eagle-import") (part "RR1206R-1.0K-1%-1206-0.25W"))
    )
    (comp (ref "R204")
      (value "1K")
      (footprint "eagle-import:R1206")
      (fields (field (name "POWER") "0.25"))
      (libsource (lib "eagle-import") (part "RR1206R-1.0K-1%-1206-0.25W"))
    )
    (comp (ref "R205")
      (value "1K")
      (footprint "eagle-import:R1206")
      (fields (field (name "POWER") "0.25"))
      (libsource (lib "eagle-import") (part "RR1206R-1.0K-1%-1206-0.25W"))
    )
    (comp (ref "R206")
      (value "1K")
      (footprint "eagle-import:R1206")
      (fields (field (name "POWER") "0.25"))
      (libsource (lib "eagle-import") (part "RR1206R-1.0K-1%-1206-0.25W"))
    )
    (comp (ref "R207")
      (value "1.0K")
      (footprint "eagle-import:0805_IPC-7351B")
      (libsource (lib "eagle-import") (part "R0805_IPCR-1.0K-0.1%-0805-0.1W"))
    )
    (comp (ref "R208")
      (value "1K")
      (footprint "eagle-import:R1206")
      (fields (field (name "POWER") "0.25"))
      (libsource (lib "eagle-import") (part "RR1206R-1.0K-1%-1206-0.25W"))
    )
    (comp (ref "R209")
      (value "1.0K")
      (footprint "eagle-import:0805_IPC-7351B")
      (libsource (lib "eagle-import") (part "R0805_IPCR-1.0K-0.1%-0805-0.1W"))
    )
    (comp (ref "R210")
      (value "1K")
      (footprint "eagle-import:R1206")
      (fields (field (name "POWER") "0.25"))
      (libsource (lib "eagle-import") (part "RR1206R-1.0K-1%-1206-0.25W"))
    )
    (comp (ref "R211")
      (value "1.0K")
      (footprint "eagle-import:0805_IPC-7351B")
      (libsource (lib "eagle-import") (part "R0805_IPCR-1.0K-0.1%-0805-0.1W"))
    )
    (comp (ref "R212")
      (value "1.0K")
      (footprint "eagle-import:0805_IPC-7351B")
      (libsource (lib "eagle-import") (part "R0805_IPCR-1.0K-0.1%-0805-0.1W"))
    )
    (comp (ref "R213")
      (value "1.0K")
      (footprint "eagle-import:0805_IPC-7351B")
      (libsource (lib "eagle-import") (part "R0805_IPCR-1.0K-0.1%-0805-0.1W"))
    )
    (comp (ref "R214")
      (value "1.0K")
      (footprint "eagle-import:0805_IPC-7351B")
      (libsource (lib "eagle-import") (part "R0805_IPCR-1.0K-0.1%-0805-0.1W"))
    )
    (comp (ref "R215")
      (value "1.0K")
      (footprint "eagle-import:0805_IPC-7351B")
      (libsource (lib "eagle-import") (part "R0805_IPCR-1.0K-0.1%-0805-0.1W"))
    )
    (comp (ref "R216")
      (value "1.0K")
      (footprint "eagle-import:0805_IPC-7351B")
      (libsource (lib "eagle-import") (part "R0805_IPCR-1.0K-0.1%-0805-0.1W"))
    )
    (comp (ref "R217")
      (value "1K")
      (footprint "eagle-import:R2512")
      (fields (field (name "POWER") "1"))
      (libsource (lib "eagle-import") (part "RR2512R-1K-1%-2512-1W"))
    )
    (comp (ref "R218")
      (value "1K")
      (footprint "eagle-import:R2512")
      (fields (field (name "POWER") "1"))
      (libsource (lib "eagle-import") (part "RR2512R-1K-1%-2512-1W"))
    )
    (comp (ref "R219")
      (value "1K")
      (footprint "eagle-import:R2512")
      (fields (field (name "POWER") "1"))
      (libsource (lib "eagle-import") (part "RR2512R-1K-1%-2512-1W"))
    )
    (comp (ref "R220")
      (value "1K")
      (footprint "eagle-import:R2512")
      (fields (field (name "POWER") "1"))
      (libsource (lib "eagle-import") (part "RR2512R-1K-1%-2512-1W"))
    )
    (comp (ref "R221")
      (value "1K")
      (footprint "eagle-import:R2512")
      (fields (field (name "POWER") "1"))
      (libsource (lib "eagle-import") (part "RR2512R-1K-1%-2512-1W"))
    )
    (comp (ref "R222")
      (value "1K")
      (footprint "eagle-import:R2512")
      (fields (field (name "POWER") "1"))
      (libsource (lib "eagle-import") (part "RR2512R-1K-1%-2512-1W"))
    )
    (comp (ref "R223")
      (value "1K")
      (footprint "eagle-import:R2512")
      (fields (field (name "POWER") "1"))
      (libsource (lib "eagle-import") (part "RR2512R-1K-1%-2512-1W"))
    )
    (comp (ref "R224")
      (value "1K")
      (footprint "eagle-import:R2512")
      (fields (field (name "POWER") "1"))
      (libsource (lib "eagle-import") (part "RR2512R-1K-1%-2512-1W"))
    )
    (comp (ref "R225")
      (value "1K")
      (footprint "eagle-import:R2512")
      (fields (field (name "POWER") "1"))
      (libsource (lib "eagle-import") (part "RR2512R-1K-1%-2512-1W"))
    )
    (comp (ref "R226")
      (value "1K")
      (footprint "eagle-import:R2512")
      (fields (field (name "POWER") "1"))
      (libsource (lib "eagle-import") (part "RR2512R-1K-1%-2512-1W"))
    )
    (comp (ref "R227")
      (value "1K")
      (footprint "eagle-import:R2512")
      (fields (field (name "POWER") "1"))
      (libsource (lib "eagle-import") (part "RR2512R-1K-1%-2512-1W"))
    )
    (comp (ref "R228")
      (value "1K")
      (footprint "eagle-import:R2512")
      (fields (field (name "POWER") "1"))
      (libsource (lib "eagle-import") (part "RR2512R-1K-1%-2512-1W"))
    )
    (comp (ref "R229")
      (value "1.0K")
      (footprint "eagle-import:0805_IPC-7351B")
      (libsource (lib "eagle-import") (part "R0805_IPCR-1.0K-0.1%-0805-0.1W"))
    )
    (comp (ref "R230")
      (value "1.0K")
      (footprint "eagle-import:0805_IPC-7351B")
      (libsource (lib "eagle-import") (part "R0805_IPCR-1.0K-0.1%-0805-0.1W"))
    )
    (comp (ref "TP7")
      (value "PROBE_TPTP_5MM")
      (footprint "eagle-import:PROBE_TP_5MM")
      (libsource (lib "eagle-import") (part "PROBE_TPTP_5MM"))
    )
    (comp (ref "TP8")
      (value "PROBE_TPTP_7P5MM")
      (footprint "eagle-import:PROBE_TP_7P5MM")
      (libsource (lib "eagle-import") (part "PROBE_TPTP_7P5MM"))
    )
    (comp (ref "TP9")
      (value "PROBE_TPTP_5MM")
      (footprint "eagle-import:PROBE_TP_5MM")
      (libsource (lib "eagle-import") (part "PROBE_TPTP_5MM"))
    )
    (comp (ref "TP10")
      (value "PROBE_TPTP_5MM")
      (footprint "eagle-import:PROBE_TP_5MM")
      (libsource (lib "eagle-import") (part "PROBE_TPTP_5MM"))
    )
    (comp (ref "TP16")
      (value "PROBE_TPTP_5MM")
      (footprint "eagle-import:PROBE_TP_5MM")
      (libsource (lib "eagle-import") (part "PROBE_TPTP_5MM"))
    )
    (comp (ref "TP17")
      (value "PROBE_TPTP_7P5MM")
      (footprint "eagle-import:PROBE_TP_7P5MM")
      (libsource (lib "eagle-import") (part "PROBE_TPTP_7P5MM"))
    )
  )
  (nets
    (net (code "1") (name "+5V") (class "Default")
      (node (ref "C306") (pin "1") (pinfunction "1_1") (pintype "passive"))
      (node (ref "C407") (pin "1") (pinfunction "1_1") (pintype "passive"))
      (node (ref "C410") (pin "+") (pinfunction "+_+") (pintype "passive"))
      (node (ref "IC301") (pin "5") (pinfunction "VCC_5") (pintype "power_in"))
      (node (ref "IC402") (pin "OUT") (pinfunction "OUT_OUT") (pintype "passive"))
      (node (ref "LED301") (pin "A") (pinfunction "A_A") (pintype "passive"))
      (node (ref "LED402") (pin "A") (pinfunction "A_A") (pintype "passive"))
      (node (ref "R301") (pin "3") (pinfunction "E_3") (pintype "passive"))
      (node (ref "R408") (pin "1") (pinfunction "1_1") (pintype "passive"))
    )
    (net (code "2") (name "+12V") (class "Default")
      (node (ref "C305") (pin "1") (pinfunction "1_1") (pintype "passive"))
      (node (ref "C406") (pin "1") (pinfunction "1_1") (pintype "passive"))
      (node (ref "C409") (pin "+") (pinfunction "+_+") (pintype "passive"))
      (node (ref "IC302") (pin "4") (pinfunction "V+_4") (pintype "power_in"))
      (node (ref "IC401") (pin "OUT") (pinfunction "OUT_OUT") (pintype "passive"))
      (node (ref "J402") (pin "2") (pinfunction "2_2") (pintype "passive"))
      (node (ref "LED401") (pin "A") (pinfunction "A_A") (pintype "passive"))
      (node (ref "T301") (pin "C") (pinfunction "C_C") (pintype "passive"))
    )
    (net (code "3") (name "ABN1") (class "Default")
      (node (ref "R103") (pin "1") (pinfunction "1_1") (pintype "passive"))
      (node (ref "R105") (pin "1") (pinfunction "1_1") (pintype "passive"))
      (node (ref "R202") (pin "1") (pinfunction "1_1") (pintype "passive"))
      (node (ref "R204") (pin "1") (pinfunction "1_1") (pintype "passive"))
      (node (ref "T101") (pin "11") (pinfunction "F2_11") (pintype "passive"))
      (node (ref "TP18") (pin "TP") (pinfunction "1_TP") (pintype "passive"))
    )
    (net (code "4") (name "ABP1") (class "Default")
      (node (ref "R102") (pin "1") (pinfunction "1_1") (pintype "passive"))
      (node (ref "R104") (pin "1") (pinfunction "1_1") (pintype "passive"))
      (node (ref "R201") (pin "1") (pinfunction "1_1") (pintype "passive"))
      (node (ref "R203") (pin "1") (pinfunction "1_1") (pintype "passive"))
      (node (ref "T101") (pin "1") (pinfunction "S1_1") (pintype "passive"))
      (node (ref "TP19") (pin "TP") (pinfunction "1_TP") (pintype "passive"))
    )
    (net (code "5") (name "AN2") (class "Default")
      (node (ref "C107") (pin "2") (pinfunction "2_2") (pintype "passive"))
      (node (ref "R105") (pin "2") (pinfunction "2_2") (pintype "passive"))
      (node (ref "R107") (pin "1") (pinfunction "1_1") (pintype "passive"))
    )
    (net (code "6") (name "AN3") (class "Default")
      (node (ref "C107") (pin "1") (pinfunction "1_1") (pintype "passive"))
      (node (ref "L102") (pin "1") (pinfunction "1_1") (pintype "passive"))
      (node (ref "R111") (pin "2") (pinfunction "2_2") (pintype "passive"))
      (node (ref "R113") (pin "1") (pinfunction "1_1") (pintype "passive"))
      (node (ref "R115") (pin "1") (pinfunction "1_1") (pintype "passive"))
    )
    (net (code "7") (name "AN4") (class "Default")
      (node (ref "L102") (pin "2") (pinfunction "2_2") (pintype "passive"))
      (node (ref "Q102") (pin "G") (pinfunction "G_G") (pintype "passive"))
      (node (ref "R115") (pin "2") (pinfunction "2_2") (pintype "passive"))
      (node (ref "R117") (pin "1") (pinfunction "1_1") (pintype "passive"))
      (node (ref "R120") (pin "1") (pinfunction "1_1") (pintype "passive"))
      (node (ref "R121") (pin "1") (pinfunction "1_1") (pintype "passive"))
      (node (ref "TP3") (pin "TP") (pinfunction "1_TP") (pintype "passive"))
    )
    (net (code "8") (name "AN5") (class "Default")
      (node (ref "Q102") (pin "S") (pinfunction "S_S") (pintype "passive"))
      (node (ref "R123") (pin "1") (pinfunction "1_1") (pintype "passive"))
      (node (ref "R125") (pin "1") (pinfunction "1_1") (pintype "passive"))
      (node (ref "R127") (pin "1") (pinfunction "1_1") (pintype "passive"))
      (node (ref "R129") (pin "1") (pinfunction "1_1") (pintype "passive"))
      (node (ref "R131") (pin "1") (pinfunction "1_1") (pintype "passive"))
      (node (ref "TP6") (pin "TP") (pinfunction "1_TP") (pintype "passive"))
    )
    (net (code "9") (name "AN6") (class "Default")
      (node (ref "C115") (pin "1") (pinfunction "1_1") (pintype "passive"))
      (node (ref "R131") (pin "2") (pinfunction "2_2") (pintype "passive"))
      (node (ref "TP15") (pin "TP") (pinfunction "1_TP") (pintype "passive"))
    )
    (net (code "10") (name "AP2") (class "Default")
      (node (ref "C105") (pin "2") (pinfunction "2_2") (pintype "passive"))
      (node (ref "R104") (pin "2") (pinfunction "2_2") (pintype "passive"))
      (node (ref "R106") (pin "1") (pinfunction "1_1") (pintype "passive"))
    )
    (net (code "11") (name "AP3") (class "Default")
      (node (ref "C105") (pin "1") (pinfunction "1_1") (pintype "passive"))
      (node (ref "L101") (pin "1") (pinfunction "1_1") (pintype "passive"))
      (node (ref "R109") (pin "2") (pinfunction "2_2") (pintype "passive"))
      (node (ref "R112") (pin "1") (pinfunction "1_1") (pintype "passive"))
      (node (ref "R114") (pin "1") (pinfunction "1_1") (pintype "passive"))
    )
    (net (code "12") (name "AP4") (class "Default")
      (node (ref "L101") (pin "2") (pinfunction "2_2") (pintype "passive"))
      (node (ref "Q101") (pin "G") (pinfunction "G_G") (pintype "passive"))
      (node (ref "R114") (pin "2") (pinfunction "2_2") (pintype "passive"))
      (node (ref "R116") (pin "1") (pinfunction "1_1") (pintype "passive"))
      (node (ref "R118") (pin "1") (pinfunction "1_1") (pintype "passive"))
      (node (ref "R119") (pin "1") (pinfunction "1_1") (pintype "passive"))
      (node (ref "TP1") (pin "TP") (pinfunction "1_TP") (pintype "passive"))
    )
    (net (code "13") (name "AP5") (class "Default")
      (node (ref "Q101") (pin "S") (pinfunction "S_S") (pintype "passive"))
      (node (ref "Q2") (pin "S") (pinfunction "S_S") (pintype "passive"))
      (node (ref "R122") (pin "1") (pinfunction "1_1") (pintype "passive"))
      (node (ref "R124") (pin "1") (pinfunction "1_1") (pintype "passive"))
      (node (ref "R126") (pin "1") (pinfunction "1_1") (pintype "passive"))
      (node (ref "R128") (pin "1") (pinfunction "1_1") (pintype "passive"))
      (node (ref "R130") (pin "1") (pinfunction "1_1") (pintype "passive"))
      (node (ref "R2") (pin "1") (pinfunction "1_1") (pintype "passive"))
      (node (ref "TP5") (pin "TP") (pinfunction "1_TP") (pintype "passive"))
    )
    (net (code "14") (name "AP6") (class "Default")
      (node (ref "C114") (pin "1") (pinfunction "1_1") (pintype "passive"))
      (node (ref "R130") (pin "2") (pinfunction "2_2") (pintype "passive"))
      (node (ref "TP14") (pin "TP") (pinfunction "1_TP") (pintype "passive"))
    )
    (net (code "15") (name "BN2") (class "Default")
      (node (ref "C204") (pin "2") (pinfunction "2_2") (pintype "passive"))
      (node (ref "R204") (pin "2") (pinfunction "2_2") (pintype "passive"))
      (node (ref "R206") (pin "1") (pinfunction "1_1") (pintype "passive"))
    )
    (net (code "16") (name "BN3") (class "Default")
      (node (ref "C204") (pin "1") (pinfunction "1_1") (pintype "passive"))
      (node (ref "L202") (pin "1") (pinfunction "1_1") (pintype "passive"))
      (node (ref "R210") (pin "2") (pinfunction "2_2") (pintype "passive"))
      (node (ref "R212") (pin "1") (pinfunction "1_1") (pintype "passive"))
      (node (ref "R214") (pin "1") (pinfunction "1_1") (pintype "passive"))
    )
    (net (code "17") (name "BN4") (class "Default")
      (node (ref "L202") (pin "2") (pinfunction "2_2") (pintype "passive"))
      (node (ref "Q202") (pin "G") (pinfunction "G_G") (pintype "passive"))
      (node (ref "R214") (pin "2") (pinfunction "2_2") (pintype "passive"))
      (node (ref "R216") (pin "1") (pinfunction "1_1") (pintype "passive"))
      (node (ref "R219") (pin "1") (pinfunction "1_1") (pintype "passive"))
      (node (ref "R220") (pin "1") (pinfunction "1_1") (pintype "passive"))
      (node (ref "TP9") (pin "TP") (pinfunction "1_TP") (pintype "passive"))
    )
    (net (code "18") (name "BN5") (class "Default")
      (node (ref "Q202") (pin "S") (pinfunction "S_S") (pintype "passive"))
      (node (ref "R222") (pin "1") (pinfunction "1_1") (pintype "passive"))
      (node (ref "R224") (pin "1") (pinfunction "1_1") (pintype "passive"))
      (node (ref "R226") (pin "1") (pinfunction "1_1") (pintype "passive"))
      (node (ref "R228") (pin "1") (pinfunction "1_1") (pintype "passive"))
      (node (ref "R230") (pin "1") (pinfunction "1_1") (pintype "passive"))
      (node (ref "TP10") (pin "TP") (pinfunction "1_TP") (pintype "passive"))
    )
    (net (code "19") (name "BN6") (class "Default")
      (node (ref "C212") (pin "1") (pinfunction "1_1") (pintype "passive"))
      (node (ref "R230") (pin "2") (pinfunction "2_2") (pintype "passive"))
      (node (ref "TP17") (pin "TP") (pinfunction "1_TP") (pintype "passive"))
    )
    (net (code "20") (name "BP2") (class "Default")
      (node (ref "C202") (pin "2") (pinfunction "2_2") (pintype "passive"))
      (node (ref "R203") (pin "2") (pinfunction "2_2") (pintype "passive"))
      (node (ref "R205") (pin "1") (pinfunction "1_1") (pintype "passive"))
    )
    (net (code "21") (name "BP3") (class "Default")
      (node (ref "C202") (pin "1") (pinfunction "1_1") (pintype "passive"))
      (node (ref "L201") (pin "1") (pinfunction "1_1") (pintype "passive"))
      (node (ref "R208") (pin "2") (pinfunction "2_2") (pintype "passive"))
      (node (ref "R211") (pin "1") (pinfunction "1_1") (pintype "passive"))
      (node (ref "R213") (pin "1") (pinfunction "1_1") (pintype "passive"))
    )
    (net (code "22") (name "BP4") (class "Default")
      (node (ref "L201") (pin "2") (pinfunction "2_2") (pintype "passive"))
      (node (ref "Q201") (pin "G") (pinfunction "G_G") (pintype "passive"))
      (node (ref "R213") (pin "2") (pinfunction "2_2") (pintype "passive"))
      (node (ref "R215") (pin "1") (pinfunction "1_1") (pintype "passive"))
      (node (ref "R217") (pin "1") (pinfunction "1_1") (pintype "passive"))
      (node (ref "R218") (pin "1") (pinfunction "1_1") (pintype "passive"))
      (node (ref "TP7") (pin "TP") (pinfunction "1_TP") (pintype "passive"))
    )
    (net (code "23") (name "BP5") (class "Default")
      (node (ref "Q201") (pin "S") (pinfunction "S_S") (pintype "passive"))
      (node (ref "R221") (pin "1") (pinfunction "1_1") (pintype "passive"))
      (node (ref "R223") (pin "1") (pinfunction "1_1") (pintype "passive"))
      (node (ref "R225") (pin "1") (pinfunction "1_1") (pintype "passive"))
      (node (ref "R227") (pin "1") (pinfunction "1_1") (pintype "passive"))
      (node (ref "R229") (pin "1") (pinfunction "1_1") (pintype "passive"))
      (node (ref "TP8") (pin "TP") (pinfunction "1_TP") (pintype "passive"))
    )
    (net (code "24") (name "BP6") (class "Default")
      (node (ref "C211") (pin "1") (pinfunction "1_1") (pintype "passive"))
      (node (ref "R229") (pin "2") (pinfunction "2_2") (pintype "passive"))
      (node (ref "TP16") (pin "TP") (pinfunction "1_TP") (pintype "passive"))
    )
    (net (code "25") (name "DRAINS_NEG") (class "Default")
      (node (ref "C113") (pin "2") (pinfunction "2_2") (pintype "passive"))
      (node (ref "C117") (pin "2") (pinfunction "2_2") (pintype "passive"))
      (node (ref "C210") (pin "2") (pinfunction "2_2") (pintype "passive"))
      (node (ref "L104") (pin "1") (pinfunction "1_1") (pintype "passive"))
      (node (ref "Q102") (pin "D") (pinfunction "D_D") (pintype "passive"))
      (node (ref "Q202") (pin "D") (pinfunction "D_D") (pintype "passive"))
      (node (ref "T102") (pin "8") (pinfunction "F5_8") (pintype "passive"))
      (node (ref "TP4") (pin "TP") (pinfunction "1_TP") (pintype "passive"))
    )
    (net (code "26") (name "DRAINS_POS") (class "Default")
      (node (ref "C1") (pin "2") (pinfunction "2_2") (pintype "passive"))
      (node (ref "C112") (pin "2") (pinfunction "2_2") (pintype "passive"))
      (node (ref "C116") (pin "2") (pinfunction "2_2") (pintype "passive"))
      (node (ref "C209") (pin "2") (pinfunction "2_2") (pintype "passive"))
      (node (ref "C3") (pin "2") (pinfunction "2_2") (pintype "passive"))
      (node (ref "L1") (pin "1") (pinfunction "1_1") (pintype "passive"))
      (node (ref "L103") (pin "1") (pinfunction "1_1") (pintype "passive"))
      (node (ref "Q101") (pin "D") (pinfunction "D_D") (pintype "passive"))
      (node (ref "Q2") (pin "D") (pinfunction "D_D") (pintype "passive"))
      (node (ref "Q201") (pin "D") (pinfunction "D_D") (pintype "passive"))
      (node (ref "T102") (pin "6") (pinfunction "S6_6") (pintype "passive"))
      (node (ref "TP2") (pin "TP") (pinfunction "1_TP") (pintype "passive"))
      (node (ref "TP20") (pin "TP") (pinfunction "1_TP") (pintype "passive"))
    )
    (net (code "27") (name "GBIAS") (class "Default")
      (node (ref "R108") (pin "1") (pinfunction "1_1") (pintype "passive"))
      (node (ref "R110") (pin "1") (pinfunction "1_1") (pintype "passive"))
      (node (ref "R207") (pin "1") (pinfunction "1_1") (pintype "passive"))
      (node (ref "R209") (pin "1") (pinfunction "1_1") (pintype "passive"))
      (node (ref "R316") (pin "2") (pinfunction "2_2") (pintype "passive"))
      (node (ref "R317") (pin "2") (pinfunction "2_2") (pintype "passive"))
      (node (ref "T301") (pin "E") (pinfunction "E_E") (pintype "passive"))
      (node (ref "T302") (pin "E") (pinfunction "E_E") (pintype "passive"))
      (node (ref "TP11") (pin "TP") (pinfunction "1_TP") (pintype "passive"))
    )
    (net (code "28") (name "GND") (class "Default")
      (node (ref "C104") (pin "2") (pinfunction "2_2") (pintype "passive"))
      (node (ref "C106") (pin "2") (pinfunction "2_2") (pintype "passive"))
      (node (ref "C108") (pin "2") (pinfunction "2_2") (pintype "passive"))
      (node (ref "C109") (pin "2") (pinfunction "2_2") (pintype "passive"))
      (node (ref "C110") (pin "2") (pinfunction "2_2") (pintype "passive"))
      (node (ref "C111") (pin "2") (pinfunction "2_2") (pintype "passive"))
      (node (ref "C114") (pin "2") (pinfunction "2_2") (pintype "passive"))
      (node (ref "C115") (pin "2") (pinfunction "2_2") (pintype "passive"))
      (node (ref "C201") (pin "2") (pinfunction "2_2") (pintype "passive"))
      (node (ref "C203") (pin "2") (pinfunction "2_2") (pintype "passive"))
      (node (ref "C205") (pin "2") (pinfunction "2_2") (pintype "passive"))
      (node (ref "C206") (pin "2") (pinfunction "2_2") (pintype "passive"))
      (node (ref "C207") (pin "2") (pinfunction "2_2") (pintype "passive"))
      (node (ref "C208") (pin "2") (pinfunction "2_2") (pintype "passive"))
      (node (ref "C211") (pin "2") (pinfunction "2_2") (pintype "passive"))
      (node (ref "C212") (pin "2") (pinfunction "2_2") (pintype "passive"))
      (node (ref "C301") (pin "2") (pinfunction "2_2") (pintype "passive"))
      (node (ref "C302") (pin "2") (pinfunction "2_2") (pintype "passive"))
      (node (ref "C303") (pin "2") (pinfunction "2_2") (pintype "passive"))
      (node (ref "C305") (pin "2") (pinfunction "2_2") (pintype "passive"))
      (node (ref "C306") (pin "2") (pinfunction "2_2") (pintype "passive"))
      (node (ref "C401") (pin "-") (pinfunction "-_-") (pintype "passive"))
      (node (ref "C402") (pin "2") (pinfunction "2_2") (pintype "passive"))
      (node (ref "C403") (pin "2") (pinfunction "2_2") (pintype "passive"))
      (node (ref "C404") (pin "2") (pinfunction "2_2") (pintype "passive"))
      (node (ref "C405") (pin "2") (pinfunction "2_2") (pintype "passive"))
      (node (ref "C406") (pin "2") (pinfunction "2_2") (pintype "passive"))
      (node (ref "C407") (pin "2") (pinfunction "2_2") (pintype "passive"))
      (node (ref "C408") (pin "2") (pinfunction "2_2") (pintype "passive"))
      (node (ref "C409") (pin "-") (pinfunction "-_-") (pintype "passive"))
      (node (ref "C410") (pin "-") (pinfunction "-_-") (pintype "passive"))
      (node (ref "C411") (pin "2") (pinfunction "2_2") (pintype "passive"))
      (node (ref "C412") (pin "2") (pinfunction "2_2") (pintype "passive"))
      (node (ref "C413") (pin "2") (pinfunction "2_2") (pintype "passive"))
      (node (ref "D401") (pin "A") (pinfunction "A1_A") (pintype "passive"))
      (node (ref "H401") (pin "B3,2") (pinfunction "MOUNT_B3,2") (pintype "passive"))
      (node (ref "H402") (pin "B3,2") (pinfunction "MOUNT_B3,2") (pintype "passive"))
      (node (ref "H403") (pin "B3,2") (pinfunction "MOUNT_B3,2") (pintype "passive"))
      (node (ref "H404") (pin "B3,2") (pinfunction "MOUNT_B3,2") (pintype "passive"))
      (node (ref "IC301") (pin "3") (pinfunction "GND_3") (pintype "power_in"))
      (node (ref "IC302") (pin "11") (pinfunction "V-_11") (pintype "power_in"))
      (node (ref "IC401") (pin "GND") (pinfunction "GND_GND") (pintype "input"))
      (node (ref "IC402") (pin "GND") (pinfunction "GND_GND") (pintype "input"))
      (node (ref "J101") (pin "G1") (pinfunction "GND1_G1") (pintype "power_in"))
      (node (ref "J101") (pin "G2") (pinfunction "GND1_G2") (pintype "power_in"))
      (node (ref "J101") (pin "G3") (pinfunction "GND1_G3") (pintype "power_in"))
      (node (ref "J101") (pin "G4") (pinfunction "GND1_G4") (pintype "power_in"))
      (node (ref "J102") (pin "G1") (pinfunction "GND1_G1") (pintype "power_in"))
      (node (ref "J102") (pin "G2") (pinfunction "GND1_G2") (pintype "power_in"))
      (node (ref "J102") (pin "G3") (pinfunction "GND1_G3") (pintype "power_in"))
      (node (ref "J102") (pin "G4") (pinfunction "GND1_G4") (pintype "power_in"))
      (node (ref "J302") (pin "G1") (pinfunction "GND1_G1") (pintype "power_in"))
      (node (ref "J302") (pin "G2") (pinfunction "GND1_G2") (pintype "power_in"))
      (node (ref "J302") (pin "G3") (pinfunction "GND1_G3") (pintype "power_in"))
      (node (ref "J302") (pin "G4") (pinfunction "GND1_G4") (pintype "power_in"))
      (node (ref "J402") (pin "1") (pinfunction "1_1") (pintype "passive"))
      (node (ref "Q301") (pin "2") (pinfunction "S_2") (pintype "passive"))
      (node (ref "R101") (pin "2") (pinfunction "2_2") (pintype "passive"))
      (node (ref "R102") (pin "2") (pinfunction "2_2") (pintype "passive"))
      (node (ref "R103") (pin "2") (pinfunction "2_2") (pintype "passive"))
      (node (ref "R106") (pin "2") (pinfunction "2_2") (pintype "passive"))
      (node (ref "R107") (pin "2") (pinfunction "2_2") (pintype "passive"))
      (node (ref "R122") (pin "2") (pinfunction "2_2") (pintype "passive"))
      (node (ref "R123") (pin "2") (pinfunction "2_2") (pintype "passive"))
      (node (ref "R124") (pin "2") (pinfunction "2_2") (pintype "passive"))
      (node (ref "R125") (pin "2") (pinfunction "2_2") (pintype "passive"))
      (node (ref "R126") (pin "2") (pinfunction "2_2") (pintype "passive"))
      (node (ref "R127") (pin "2") (pinfunction "2_2") (pintype "passive"))
      (node (ref "R128") (pin "2") (pinfunction "2_2") (pintype "passive"))
      (node (ref "R129") (pin "2") (pinfunction "2_2") (pintype "passive"))
      (node (ref "R2") (pin "2") (pinfunction "2_2") (pintype "passive"))
      (node (ref "R201") (pin "2") (pinfunction "2_2") (pintype "passive"))
      (node (ref "R202") (pin "2") (pinfunction "2_2") (pintype "passive"))
      (node (ref "R205") (pin "2") (pinfunction "2_2") (pintype "passive"))
      (node (ref "R206") (pin "2") (pinfunction "2_2") (pintype "passive"))
      (node (ref "R221") (pin "2") (pinfunction "2_2") (pintype "passive"))
      (node (ref "R222") (pin "2") (pinfunction "2_2") (pintype "passive"))
      (node (ref "R223") (pin "2") (pinfunction "2_2") (pintype "passive"))
      (node (ref "R224") (pin "2") (pinfunction "2_2") (pintype "passive"))
      (node (ref "R225") (pin "2") (pinfunction "2_2") (pintype "passive"))
      (node (ref "R226") (pin "2") (pinfunction "2_2") (pintype "passive"))
      (node (ref "R227") (pin "2") (pinfunction "2_2") (pintype "passive"))
      (node (ref "R228") (pin "2") (pinfunction "2_2") (pintype "passive"))
      (node (ref "R3") (pin "2") (pinfunction "2_2") (pintype "passive"))
      (node (ref "R301") (pin "1") (pinfunction "A_1") (pintype "passive"))
      (node (ref "R307") (pin "2") (pinfunction "2_2") (pintype "passive"))
      (node (ref "R311") (pin "2") (pinfunction "2_2") (pintype "passive"))
      (node (ref "R312") (pin "1") (pinfunction "1_1") (pintype "passive"))
      (node (ref "R406") (pin "2") (pinfunction "2_2") (pintype "passive"))
      (node (ref "R407") (pin "2") (pinfunction "2_2") (pintype "passive"))
      (node (ref "T101") (pin "10") (pinfunction "F3_10") (pintype "passive"))
      (node (ref "T102") (pin "9") (pinfunction "F4_9") (pintype "passive"))
      (node (ref "T302") (pin "C") (pinfunction "C_C") (pintype "passive"))
      (node (ref "TP1") (pin "GND") (pinfunction "GND1_GND") (pintype "power_in"))
      (node (ref "TP10") (pin "GND") (pinfunction "GND1_GND") (pintype "power_in"))
      (node (ref "TP11") (pin "GND") (pinfunction "GND1_GND") (pintype "power_in"))
      (node (ref "TP12") (pin "GND") (pinfunction "GND1_GND") (pintype "power_in"))
      (node (ref "TP13") (pin "GND") (pinfunction "GND1_GND") (pintype "power_in"))
      (node (ref "TP14") (pin "GND") (pinfunction "GND1_GND") (pintype "power_in"))
      (node (ref "TP15") (pin "GND") (pinfunction "GND1_GND") (pintype "power_in"))
      (node (ref "TP16") (pin "GND") (pinfunction "GND1_GND") (pintype "power_in"))
      (node (ref "TP17") (pin "GND") (pinfunction "GND1_GND") (pintype "power_in"))
      (node (ref "TP18") (pin "GND") (pinfunction "GND1_GND") (pintype "power_in"))
      (node (ref "TP19") (pin "GND") (pinfunction "GND1_GND") (pintype "power_in"))
      (node (ref "TP2") (pin "GND") (pinfunction "GND1_GND") (pintype "power_in"))
      (node (ref "TP20") (pin "GND") (pinfunction "GND1_GND") (pintype "power_in"))
      (node (ref "TP3") (pin "GND") (pinfunction "GND1_GND") (pintype "power_in"))
      (node (ref "TP4") (pin "GND") (pinfunction "GND1_GND") (pintype "power_in"))
      (node (ref "TP5") (pin "GND") (pinfunction "GND1_GND") (pintype "power_in"))
      (node (ref "TP6") (pin "GND") (pinfunction "GND1_GND") (pintype "power_in"))
      (node (ref "TP7") (pin "GND") (pinfunction "GND1_GND") (pintype "power_in"))
      (node (ref "TP8") (pin "GND") (pinfunction "GND1_GND") (pintype "power_in"))
      (node (ref "TP9") (pin "GND") (pinfunction "GND1_GND") (pintype "power_in"))
      (node (ref "X401") (pin "2") (pinfunction "KL_2") (pintype "passive"))
      (node (ref "X402") (pin "P1") (pinfunction "P$1_P1") (pintype "bidirectional"))
      (node (ref "X402") (pin "P2") (pinfunction "P$2_P2") (pintype "bidirectional"))
    )
    (net (code "29") (name "Net-(C1-Pad1)") (class "Default")
      (node (ref "C1") (pin "1") (pinfunction "1_1") (pintype "passive"))
      (node (ref "R1") (pin "2") (pinfunction "2_2") (pintype "passive"))
      (node (ref "R4") (pin "2") (pinfunction "2_2") (pintype "passive"))
    )
    (net (code "30") (name "Net-(C104-Pad1)") (class "Default")
      (node (ref "C104") (pin "1") (pinfunction "1_1") (pintype "passive"))
      (node (ref "R108") (pin "2") (pinfunction "2_2") (pintype "passive"))
      (node (ref "R109") (pin "1") (pinfunction "1_1") (pintype "passive"))
    )
    (net (code "31") (name "Net-(C106-Pad1)") (class "Default")
      (node (ref "C106") (pin "1") (pinfunction "1_1") (pintype "passive"))
      (node (ref "R110") (pin "2") (pinfunction "2_2") (pintype "passive"))
      (node (ref "R111") (pin "1") (pinfunction "1_1") (pintype "passive"))
    )
    (net (code "32") (name "Net-(C108-Pad1)") (class "Default")
      (node (ref "C108") (pin "1") (pinfunction "1_1") (pintype "passive"))
      (node (ref "R112") (pin "2") (pinfunction "2_2") (pintype "passive"))
    )
    (net (code "33") (name "Net-(C109-Pad1)") (class "Default")
      (node (ref "C109") (pin "1") (pinfunction "1_1") (pintype "passive"))
      (node (ref "R113") (pin "2") (pinfunction "2_2") (pintype "passive"))
    )
    (net (code "34") (name "Net-(C110-Pad1)") (class "Default")
      (node (ref "C110") (pin "1") (pinfunction "1_1") (pintype "passive"))
      (node (ref "R116") (pin "2") (pinfunction "2_2") (pintype "passive"))
    )
    (net (code "35") (name "Net-(C111-Pad1)") (class "Default")
      (node (ref "C111") (pin "1") (pinfunction "1_1") (pintype "passive"))
      (node (ref "R117") (pin "2") (pinfunction "2_2") (pintype "passive"))
    )
    (net (code "36") (name "Net-(C112-Pad1)") (class "Default")
      (node (ref "C112") (pin "1") (pinfunction "1_1") (pintype "passive"))
      (node (ref "R118") (pin "2") (pinfunction "2_2") (pintype "passive"))
      (node (ref "R119") (pin "2") (pinfunction "2_2") (pintype "passive"))
    )
    (net (code "37") (name "Net-(C113-Pad1)") (class "Default")
      (node (ref "C113") (pin "1") (pinfunction "1_1") (pintype "passive"))
      (node (ref "R120") (pin "2") (pinfunction "2_2") (pintype "passive"))
      (node (ref "R121") (pin "2") (pinfunction "2_2") (pintype "passive"))
    )
    (net (code "38") (name "Net-(C201-Pad1)") (class "Default")
      (node (ref "C201") (pin "1") (pinfunction "1_1") (pintype "passive"))
      (node (ref "R207") (pin "2") (pinfunction "2_2") (pintype "passive"))
      (node (ref "R208") (pin "1") (pinfunction "1_1") (pintype "passive"))
    )
    (net (code "39") (name "Net-(C203-Pad1)") (class "Default")
      (node (ref "C203") (pin "1") (pinfunction "1_1") (pintype "passive"))
      (node (ref "R209") (pin "2") (pinfunction "2_2") (pintype "passive"))
      (node (ref "R210") (pin "1") (pinfunction "1_1") (pintype "passive"))
    )
    (net (code "40") (name "Net-(C205-Pad1)") (class "Default")
      (node (ref "C205") (pin "1") (pinfunction "1_1") (pintype "passive"))
      (node (ref "R211") (pin "2") (pinfunction "2_2") (pintype "passive"))
    )
    (net (code "41") (name "Net-(C206-Pad1)") (class "Default")
      (node (ref "C206") (pin "1") (pinfunction "1_1") (pintype "passive"))
      (node (ref "R212") (pin "2") (pinfunction "2_2") (pintype "passive"))
    )
    (net (code "42") (name "Net-(C207-Pad1)") (class "Default")
      (node (ref "C207") (pin "1") (pinfunction "1_1") (pintype "passive"))
      (node (ref "R215") (pin "2") (pinfunction "2_2") (pintype "passive"))
    )
    (net (code "43") (name "Net-(C208-Pad1)") (class "Default")
      (node (ref "C208") (pin "1") (pinfunction "1_1") (pintype "passive"))
      (node (ref "R216") (pin "2") (pinfunction "2_2") (pintype "passive"))
    )
    (net (code "44") (name "Net-(C209-Pad1)") (class "Default")
      (node (ref "C209") (pin "1") (pinfunction "1_1") (pintype "passive"))
      (node (ref "R217") (pin "2") (pinfunction "2_2") (pintype "passive"))
      (node (ref "R218") (pin "2") (pinfunction "2_2") (pintype "passive"))
    )
    (net (code "45") (name "Net-(C210-Pad1)") (class "Default")
      (node (ref "C210") (pin "1") (pinfunction "1_1") (pintype "passive"))
      (node (ref "R219") (pin "2") (pinfunction "2_2") (pintype "passive"))
      (node (ref "R220") (pin "2") (pinfunction "2_2") (pintype "passive"))
    )
    (net (code "46") (name "Net-(C302-Pad1)") (class "Default")
      (node (ref "C302") (pin "1") (pinfunction "1_1") (pintype "passive"))
      (node (ref "R313") (pin "1") (pinfunction "1_1") (pintype "passive"))
    )
    (net (code "47") (name "Net-(C304-Pad1)") (class "Default")
      (node (ref "C304") (pin "1") (pinfunction "1_1") (pintype "passive"))
      (node (ref "R314") (pin "2") (pinfunction "2_2") (pintype "passive"))
    )
    (net (code "48") (name "Net-(C403-Pad1)") (class "Default")
      (node (ref "C403") (pin "1") (pinfunction "1_1") (pintype "passive"))
      (node (ref "IC401") (pin "IN") (pinfunction "IN_IN") (pintype "input"))
      (node (ref "R402") (pin "2") (pinfunction "2_2") (pintype "passive"))
    )
    (net (code "49") (name "Net-(C404-Pad1)") (class "Default")
      (node (ref "C404") (pin "1") (pinfunction "1_1") (pintype "passive"))
      (node (ref "IC402") (pin "IN") (pinfunction "IN_IN") (pintype "input"))
      (node (ref "R403") (pin "2") (pinfunction "2_2") (pintype "passive"))
    )
    (net (code "50") (name "Net-(C405-Pad1)") (class "Default")
      (node (ref "C405") (pin "1") (pinfunction "1_1") (pintype "passive"))
      (node (ref "L401") (pin "2") (pinfunction "2_2") (pintype "passive"))
      (node (ref "L402") (pin "1") (pinfunction "1_1") (pintype "passive"))
      (node (ref "R404") (pin "1") (pinfunction "1_1") (pintype "passive"))
      (node (ref "R405") (pin "1") (pinfunction "1_1") (pintype "passive"))
    )
    (net (code "51") (name "Net-(D401-C1)") (class "Default")
      (node (ref "D401") (pin "K") (pinfunction "C1_K") (pintype "passive"))
      (node (ref "J401") (pin "2") (pinfunction "2_2") (pintype "passive"))
      (node (ref "R401") (pin "1") (pinfunction "1_1") (pintype "passive"))
    )
    (net (code "52") (name "Net-(D402-A1)") (class "Default")
      (node (ref "D402") (pin "A") (pinfunction "A1_A") (pintype "passive"))
      (node (ref "R402") (pin "1") (pinfunction "1_1") (pintype "passive"))
      (node (ref "R403") (pin "1") (pinfunction "1_1") (pintype "passive"))
    )
    (net (code "53") (name "Net-(D402-C1)") (class "Default")
      (node (ref "C401") (pin "+") (pinfunction "+_+") (pintype "passive"))
      (node (ref "C402") (pin "1") (pinfunction "1_1") (pintype "passive"))
      (node (ref "D402") (pin "C") (pinfunction "C1_C") (pintype "passive"))
      (node (ref "L401") (pin "1") (pinfunction "1_1") (pintype "passive"))
      (node (ref "R401") (pin "2") (pinfunction "2_2") (pintype "passive"))
    )
    (net (code "54") (name "Net-(IC301A-I)") (class "Default")
      (node (ref "IC301") (pin "2") (pinfunction "I_2") (pintype "input"))
      (node (ref "R304") (pin "2") (pinfunction "2_2") (pintype "passive"))
      (node (ref "R307") (pin "1") (pinfunction "1_1") (pintype "passive"))
    )
    (net (code "55") (name "Net-(IC301A-O)") (class "Default")
      (node (ref "IC301") (pin "4") (pinfunction "O_4") (pintype "output"))
      (node (ref "Q301") (pin "1") (pinfunction "G_1") (pintype "passive"))
      (node (ref "R309") (pin "2") (pinfunction "2_2") (pintype "passive"))
    )
    (net (code "56") (name "Net-(IC302A-+IN)") (class "Default")
      (node (ref "C303") (pin "1") (pinfunction "1_1") (pintype "passive"))
      (node (ref "IC302") (pin "3") (pinfunction "+IN_3") (pintype "input"))
      (node (ref "R310") (pin "2") (pinfunction "2_2") (pintype "passive"))
      (node (ref "R311") (pin "1") (pinfunction "1_1") (pintype "passive"))
    )
    (net (code "57") (name "Net-(IC302A--IN)") (class "Default")
      (node (ref "C304") (pin "2") (pinfunction "2_2") (pintype "passive"))
      (node (ref "IC302") (pin "2") (pinfunction "-IN_2") (pintype "input"))
      (node (ref "R312") (pin "2") (pinfunction "2_2") (pintype "passive"))
      (node (ref "R313") (pin "2") (pinfunction "2_2") (pintype "passive"))
      (node (ref "R317") (pin "1") (pinfunction "1_1") (pintype "passive"))
    )
    (net (code "58") (name "Net-(IC302A-OUT)") (class "Default")
      (node (ref "IC302") (pin "1") (pinfunction "OUT_1") (pintype "output"))
      (node (ref "R314") (pin "1") (pinfunction "1_1") (pintype "passive"))
      (node (ref "R315") (pin "1") (pinfunction "1_1") (pintype "passive"))
    )
    (net (code "59") (name "Net-(IC302B-+IN)") (class "Default")
      (node (ref "IC302") (pin "5") (pinfunction "+IN_5") (pintype "input"))
      (node (ref "Q301") (pin "3") (pinfunction "D_3") (pintype "passive"))
      (node (ref "R308") (pin "2") (pinfunction "2_2") (pintype "passive"))
    )
    (net (code "60") (name "Net-(IC302B--IN)") (class "Default")
      (node (ref "IC302") (pin "6") (pinfunction "-IN_6") (pintype "input"))
      (node (ref "IC302") (pin "7") (pinfunction "OUT_7") (pintype "output"))
      (node (ref "R310") (pin "1") (pinfunction "1_1") (pintype "passive"))
      (node (ref "TP12") (pin "TP") (pinfunction "1_TP") (pintype "passive"))
    )
    (net (code "61") (name "Net-(IC302C-+IN)") (class "Default")
      (node (ref "IC302") (pin "10") (pinfunction "+IN_10") (pintype "input"))
      (node (ref "R303") (pin "2") (pinfunction "2_2") (pintype "passive"))
      (node (ref "R306") (pin "1") (pinfunction "1_1") (pintype "passive"))
    )
    (net (code "62") (name "Net-(IC302C--IN)") (class "Default")
      (node (ref "IC302") (pin "9") (pinfunction "-IN_9") (pintype "input"))
      (node (ref "JP302") (pin "1") (pinfunction "1_1") (pintype "passive"))
      (node (ref "R302") (pin "2") (pinfunction "2_2") (pintype "passive"))
      (node (ref "R305") (pin "1") (pinfunction "1_1") (pintype "passive"))
    )
    (net (code "63") (name "Net-(IC302C-OUT)") (class "Default")
      (node (ref "IC302") (pin "8") (pinfunction "OUT_8") (pintype "output"))
      (node (ref "JP302") (pin "2") (pinfunction "2_2") (pintype "passive"))
      (node (ref "R305") (pin "2") (pinfunction "2_2") (pintype "passive"))
      (node (ref "R308") (pin "1") (pinfunction "1_1") (pintype "passive"))
    )
    (net (code "64") (name "Net-(IC302D-+IN)") (class "Default")
      (node (ref "C301") (pin "1") (pinfunction "1_1") (pintype "passive"))
      (node (ref "IC302") (pin "12") (pinfunction "+IN_12") (pintype "input"))
      (node (ref "R301") (pin "2") (pinfunction "S_2") (pintype "passive"))
    )
    (net (code "65") (name "Net-(IC302D--IN)") (class "Default")
      (node (ref "IC302") (pin "13") (pinfunction "-IN_13") (pintype "input"))
      (node (ref "IC302") (pin "14") (pinfunction "OUT_14") (pintype "output"))
      (node (ref "R306") (pin "2") (pinfunction "2_2") (pintype "passive"))
      (node (ref "TP13") (pin "TP") (pinfunction "1_TP") (pintype "passive"))
    )
    (net (code "66") (name "Net-(J101-1)") (class "Default")
      (node (ref "C101") (pin "2") (pinfunction "2_2") (pintype "passive"))
      (node (ref "C102") (pin "2") (pinfunction "2_2") (pintype "passive"))
      (node (ref "C103") (pin "2") (pinfunction "2_2") (pintype "passive"))
      (node (ref "J101") (pin "C") (pinfunction "1_C") (pintype "passive"))
    )
    (net (code "67") (name "Net-(J102-1)") (class "Default")
      (node (ref "C118") (pin "2") (pinfunction "2_2") (pintype "passive"))
      (node (ref "C119") (pin "2") (pinfunction "2_2") (pintype "passive"))
      (node (ref "C120") (pin "2") (pinfunction "2_2") (pintype "passive"))
      (node (ref "J102") (pin "C") (pinfunction "1_C") (pintype "passive"))
    )
    (net (code "68") (name "Net-(J301-1)") (class "Default")
      (node (ref "J301") (pin "C") (pinfunction "1_C") (pintype "passive"))
      (node (ref "JP301") (pin "2") (pinfunction "2_2") (pintype "passive"))
      (node (ref "R302") (pin "1") (pinfunction "1_1") (pintype "passive"))
    )
    (net (code "69") (name "Net-(J301-GND1-PadG1)") (class "Default")
      (node (ref "J301") (pin "G1") (pinfunction "GND1_G1") (pintype "power_in"))
      (node (ref "J301") (pin "G2") (pinfunction "GND1_G2") (pintype "power_in"))
      (node (ref "J301") (pin "G3") (pinfunction "GND1_G3") (pintype "power_in"))
      (node (ref "J301") (pin "G4") (pinfunction "GND1_G4") (pintype "power_in"))
      (node (ref "JP301") (pin "1") (pinfunction "1_1") (pintype "passive"))
      (node (ref "R303") (pin "1") (pinfunction "1_1") (pintype "passive"))
    )
    (net (code "70") (name "Net-(J302-1)") (class "Default")
      (node (ref "J302") (pin "C") (pinfunction "1_C") (pintype "passive"))
      (node (ref "R304") (pin "1") (pinfunction "1_1") (pintype "passive"))
    )
    (net (code "71") (name "Net-(J402-Pad3)") (class "Default")
      (node (ref "J402") (pin "3") (pinfunction "3_3") (pintype "passive"))
      (node (ref "R408") (pin "2") (pinfunction "2_2") (pintype "passive"))
    )
    (net (code "72") (name "Net-(LED301-C)") (class "Default")
      (node (ref "LED301") (pin "K") (pinfunction "C_K") (pintype "passive"))
      (node (ref "R309") (pin "1") (pinfunction "1_1") (pintype "passive"))
    )
    (net (code "73") (name "Net-(LED401-C)") (class "Default")
      (node (ref "LED401") (pin "K") (pinfunction "C_K") (pintype "passive"))
      (node (ref "R406") (pin "1") (pinfunction "1_1") (pintype "passive"))
    )
    (net (code "74") (name "Net-(LED402-C)") (class "Default")
      (node (ref "LED402") (pin "K") (pinfunction "C_K") (pintype "passive"))
      (node (ref "R407") (pin "1") (pinfunction "1_1") (pintype "passive"))
    )
    (net (code "75") (name "Net-(R315-Pad2)") (class "Default")
      (node (ref "R315") (pin "2") (pinfunction "2_2") (pintype "passive"))
      (node (ref "R316") (pin "1") (pinfunction "1_1") (pintype "passive"))
      (node (ref "T301") (pin "B") (pinfunction "B_B") (pintype "passive"))
      (node (ref "T302") (pin "B") (pinfunction "B_B") (pintype "passive"))
    )
    (net (code "76") (name "Net-(T101-F1)") (class "Default")
      (node (ref "R101") (pin "1") (pinfunction "1_1") (pintype "passive"))
      (node (ref "T101") (pin "12") (pinfunction "F1_12") (pintype "passive"))
      (node (ref "T101") (pin "2") (pinfunction "S2_2") (pintype "passive"))
    )
    (net (code "77") (name "Net-(T101-F4)") (class "Default")
      (node (ref "T101") (pin "3") (pinfunction "S3_3") (pintype "passive"))
      (node (ref "T101") (pin "9") (pinfunction "F4_9") (pintype "passive"))
    )
    (net (code "78") (name "Net-(T101-F5)") (class "Default")
      (node (ref "C101") (pin "1") (pinfunction "1_1") (pintype "passive"))
      (node (ref "T101") (pin "4") (pinfunction "S4_4") (pintype "passive"))
      (node (ref "T101") (pin "8") (pinfunction "F5_8") (pintype "passive"))
    )
    (net (code "79") (name "Net-(T101-F6)") (class "Default")
      (node (ref "C102") (pin "1") (pinfunction "1_1") (pintype "passive"))
      (node (ref "T101") (pin "5") (pinfunction "S5_5") (pintype "passive"))
      (node (ref "T101") (pin "7") (pinfunction "F6_7") (pintype "passive"))
    )
    (net (code "80") (name "Net-(T101-S6)") (class "Default")
      (node (ref "C103") (pin "1") (pinfunction "1_1") (pintype "passive"))
      (node (ref "T101") (pin "6") (pinfunction "S6_6") (pintype "passive"))
    )
    (net (code "81") (name "Net-(T102-F1)") (class "Default")
      (node (ref "C119") (pin "1") (pinfunction "1_1") (pintype "passive"))
      (node (ref "T102") (pin "12") (pinfunction "F1_12") (pintype "passive"))
      (node (ref "T102") (pin "2") (pinfunction "S2_2") (pintype "passive"))
    )
    (net (code "82") (name "Net-(T102-F2)") (class "Default")
      (node (ref "C118") (pin "1") (pinfunction "1_1") (pintype "passive"))
      (node (ref "T102") (pin "11") (pinfunction "F2_11") (pintype "passive"))
      (node (ref "T102") (pin "3") (pinfunction "S3_3") (pintype "passive"))
    )
    (net (code "83") (name "Net-(T102-F3)") (class "Default")
      (node (ref "T102") (pin "10") (pinfunction "F3_10") (pintype "passive"))
      (node (ref "T102") (pin "4") (pinfunction "S4_4") (pintype "passive"))
    )
    (net (code "84") (name "Net-(T102-F6)") (class "Default")
      (node (ref "R132") (pin "2") (pinfunction "2_2") (pintype "passive"))
      (node (ref "T102") (pin "5") (pinfunction "S5_5") (pintype "passive"))
      (node (ref "T102") (pin "7") (pinfunction "F6_7") (pintype "passive"))
    )
    (net (code "85") (name "Net-(T102-S1)") (class "Default")
      (node (ref "C120") (pin "1") (pinfunction "1_1") (pintype "passive"))
      (node (ref "T102") (pin "1") (pinfunction "S1_1") (pintype "passive"))
    )
    (net (code "86") (name "Net-(X401A-KL)") (class "Default")
      (node (ref "J401") (pin "1") (pinfunction "1_1") (pintype "passive"))
      (node (ref "X401") (pin "1") (pinfunction "KL_1") (pintype "passive"))
    )
    (net (code "87") (name "VB") (class "Default")
      (node (ref "C116") (pin "1") (pinfunction "1_1") (pintype "passive"))
      (node (ref "C117") (pin "1") (pinfunction "1_1") (pintype "passive"))
      (node (ref "C3") (pin "1") (pinfunction "1_1") (pintype "passive"))
      (node (ref "C408") (pin "1") (pinfunction "1_1") (pintype "passive"))
      (node (ref "C411") (pin "1") (pinfunction "1_1") (pintype "passive"))
      (node (ref "C412") (pin "1") (pinfunction "1_1") (pintype "passive"))
      (node (ref "C413") (pin "1") (pinfunction "1_1") (pintype "passive"))
      (node (ref "L1") (pin "2") (pinfunction "2_2") (pintype "passive"))
      (node (ref "L103") (pin "2") (pinfunction "2_2") (pintype "passive"))
      (node (ref "L104") (pin "2") (pinfunction "2_2") (pintype "passive"))
      (node (ref "L402") (pin "2") (pinfunction "2_2") (pintype "passive"))
      (node (ref "R132") (pin "1") (pinfunction "1_1") (pintype "passive"))
      (node (ref "R404") (pin "2") (pinfunction "2_2") (pintype "passive"))
      (node (ref "R405") (pin "2") (pinfunction "2_2") (pintype "passive"))
    )
    (net (code "88") (name "unconnected-(J402-Pad4)") (class "Default")
      (node (ref "J402") (pin "4") (pinfunction "4_4") (pintype "passive"))
    )
    (net (code "89") (name "unconnected-(Q1-PadD)") (class "Default")
      (node (ref "Q1") (pin "D") (pinfunction "D_D") (pintype "passive"))
    )
    (net (code "90") (name "unconnected-(Q1-PadG)") (class "Default")
      (node (ref "Q1") (pin "G") (pinfunction "G_G") (pintype "passive"))
    )
    (net (code "91") (name "unconnected-(Q1-PadS)") (class "Default")
      (node (ref "Q1") (pin "S") (pinfunction "S_S") (pintype "passive"))
    )
    (net (code "92") (name "unconnected-(Q2-PadG)") (class "Default")
      (node (ref "Q2") (pin "G") (pinfunction "G_G") (pintype "passive"))
    )
    (net (code "93") (name "unconnected-(R1-Pad1)") (class "Default")
      (node (ref "R1") (pin "1") (pinfunction "1_1") (pintype "passive"))
    )
    (net (code "94") (name "unconnected-(R3-Pad1)") (class "Default")
      (node (ref "R3") (pin "1") (pinfunction "1_1") (pintype "passive"))
    )
    (net (code "95") (name "unconnected-(R4-Pad1)") (class "Default")
      (node (ref "R4") (pin "1") (pinfunction "1_1") (pintype "passive"))
    )
    (net (code "96") (name "unconnected-(R5-Pad1)") (class "Default")
      (node (ref "R5") (pin "1") (pinfunction "1_1") (pintype "passive"))
    )
    (net (code "97") (name "unconnected-(R5-Pad2)") (class "Default")
      (node (ref "R5") (pin "2") (pinfunction "2_2") (pintype "passive"))
    )
  )
)
